# led_table_final.net
KiCad netlist of a schematic drawn in EAGLE
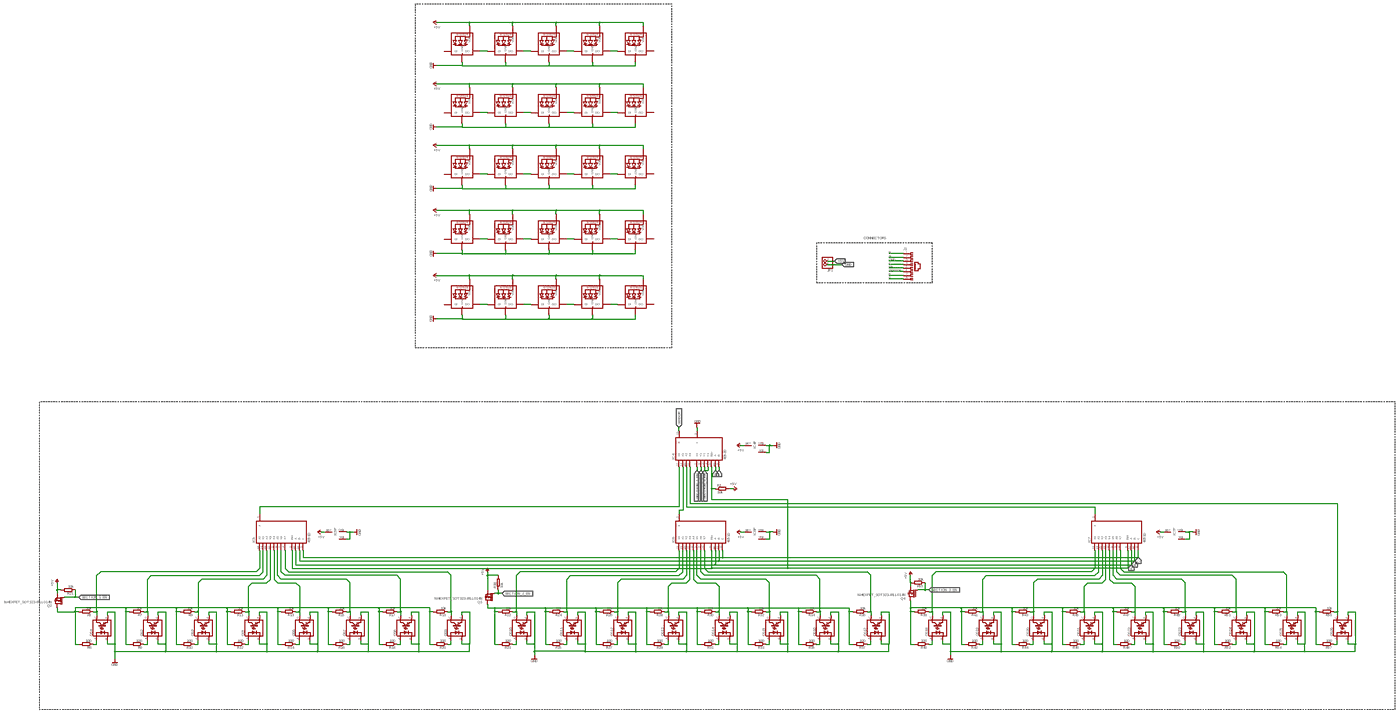
[diagram p0: schematic, sheet 1, overview]
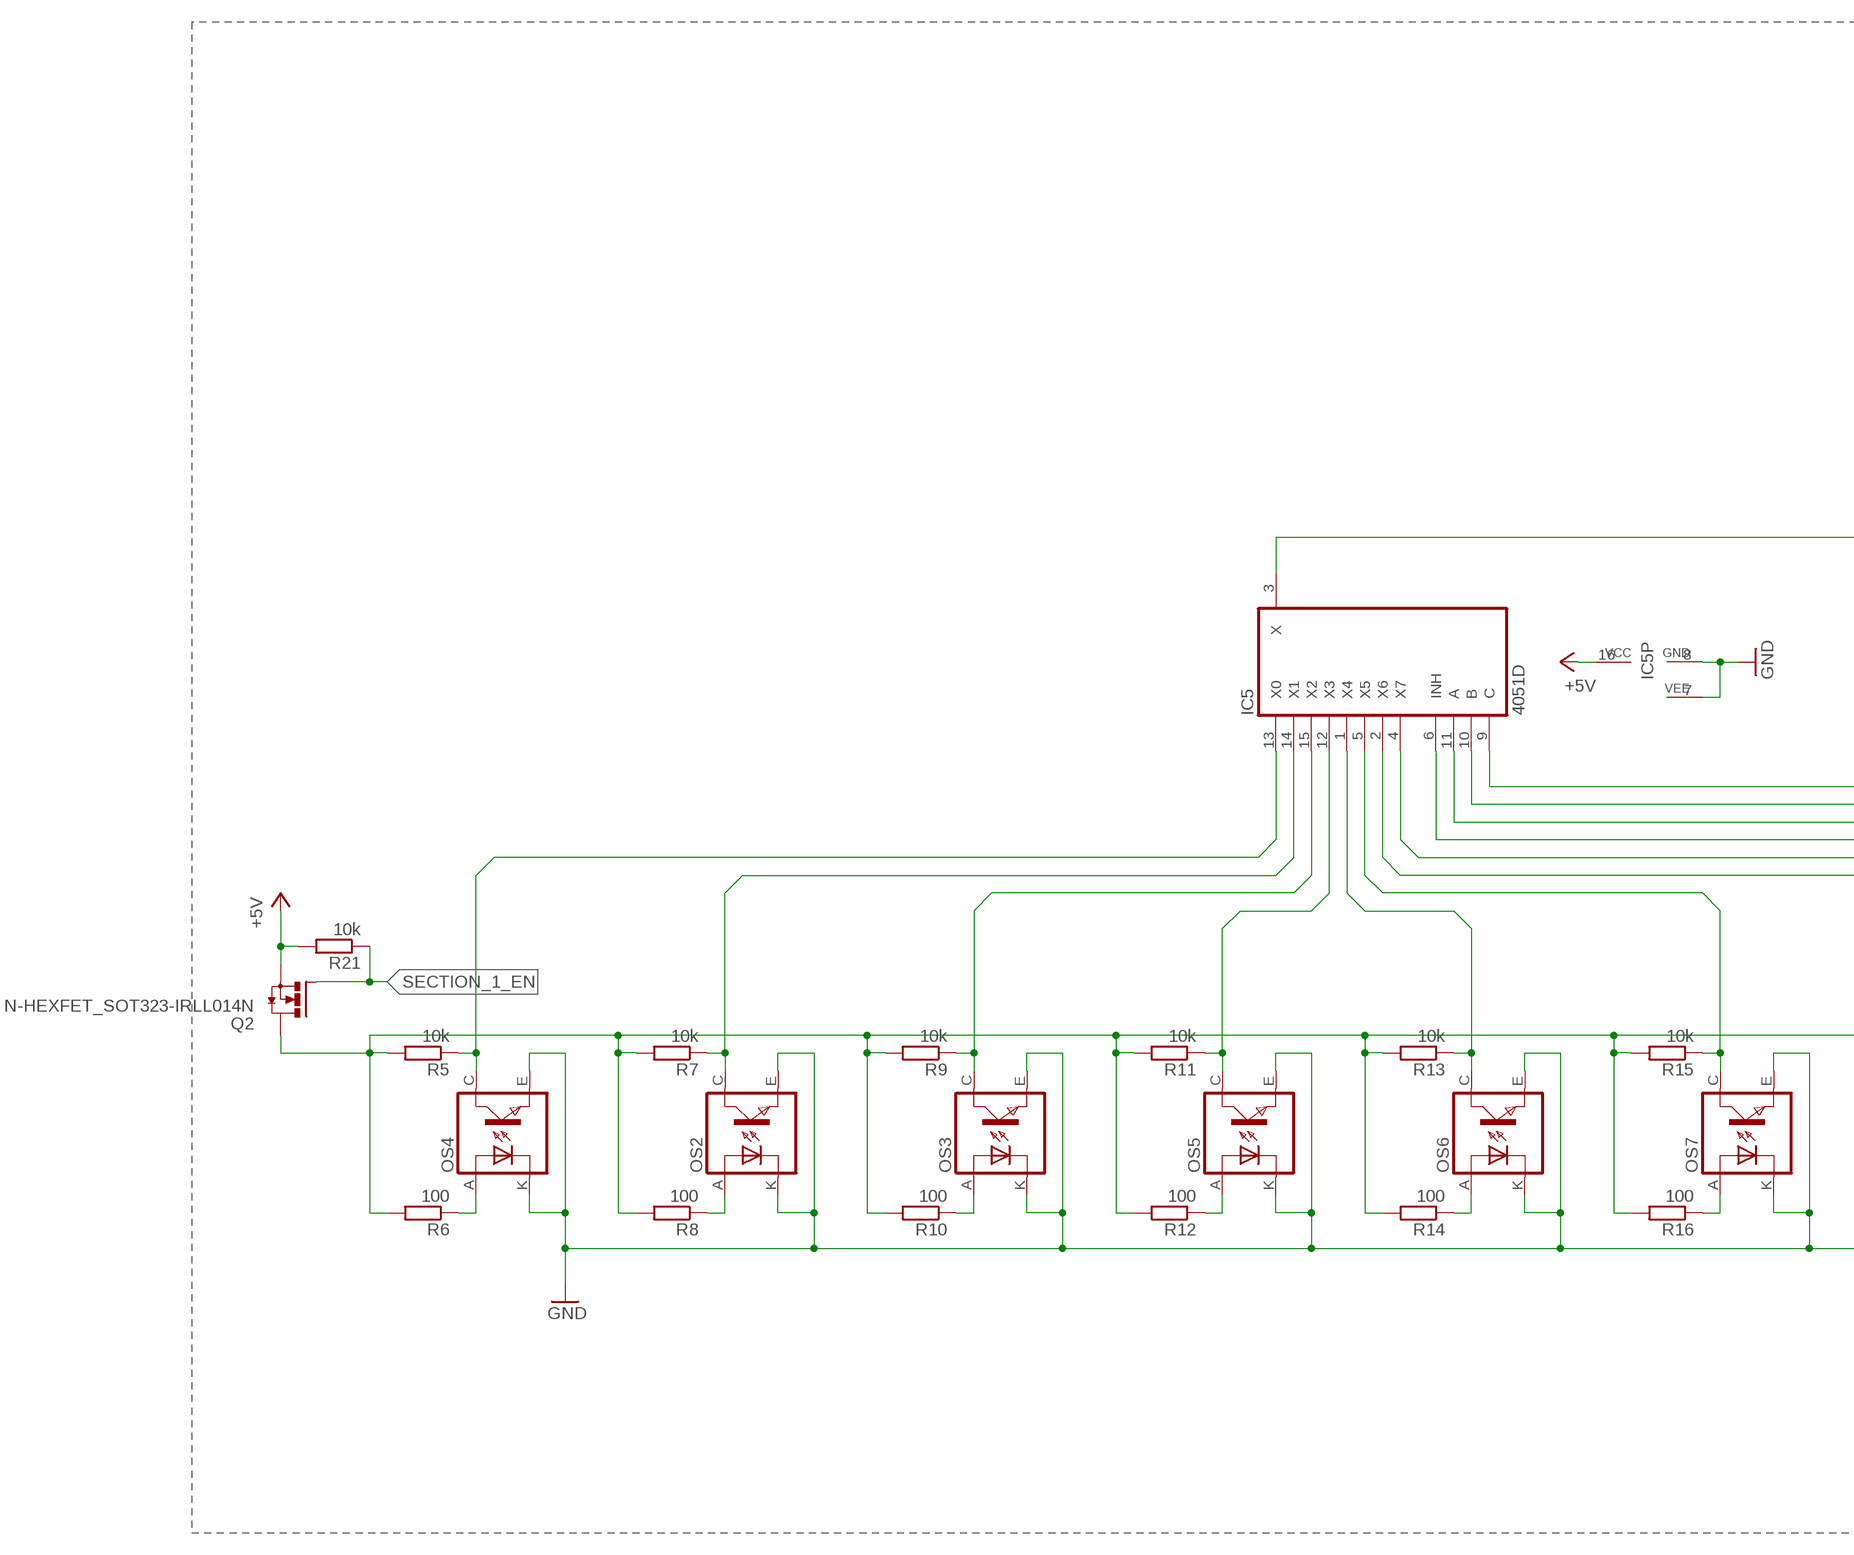
[diagram p1: schematic, sheet 1, part 1 of 4]
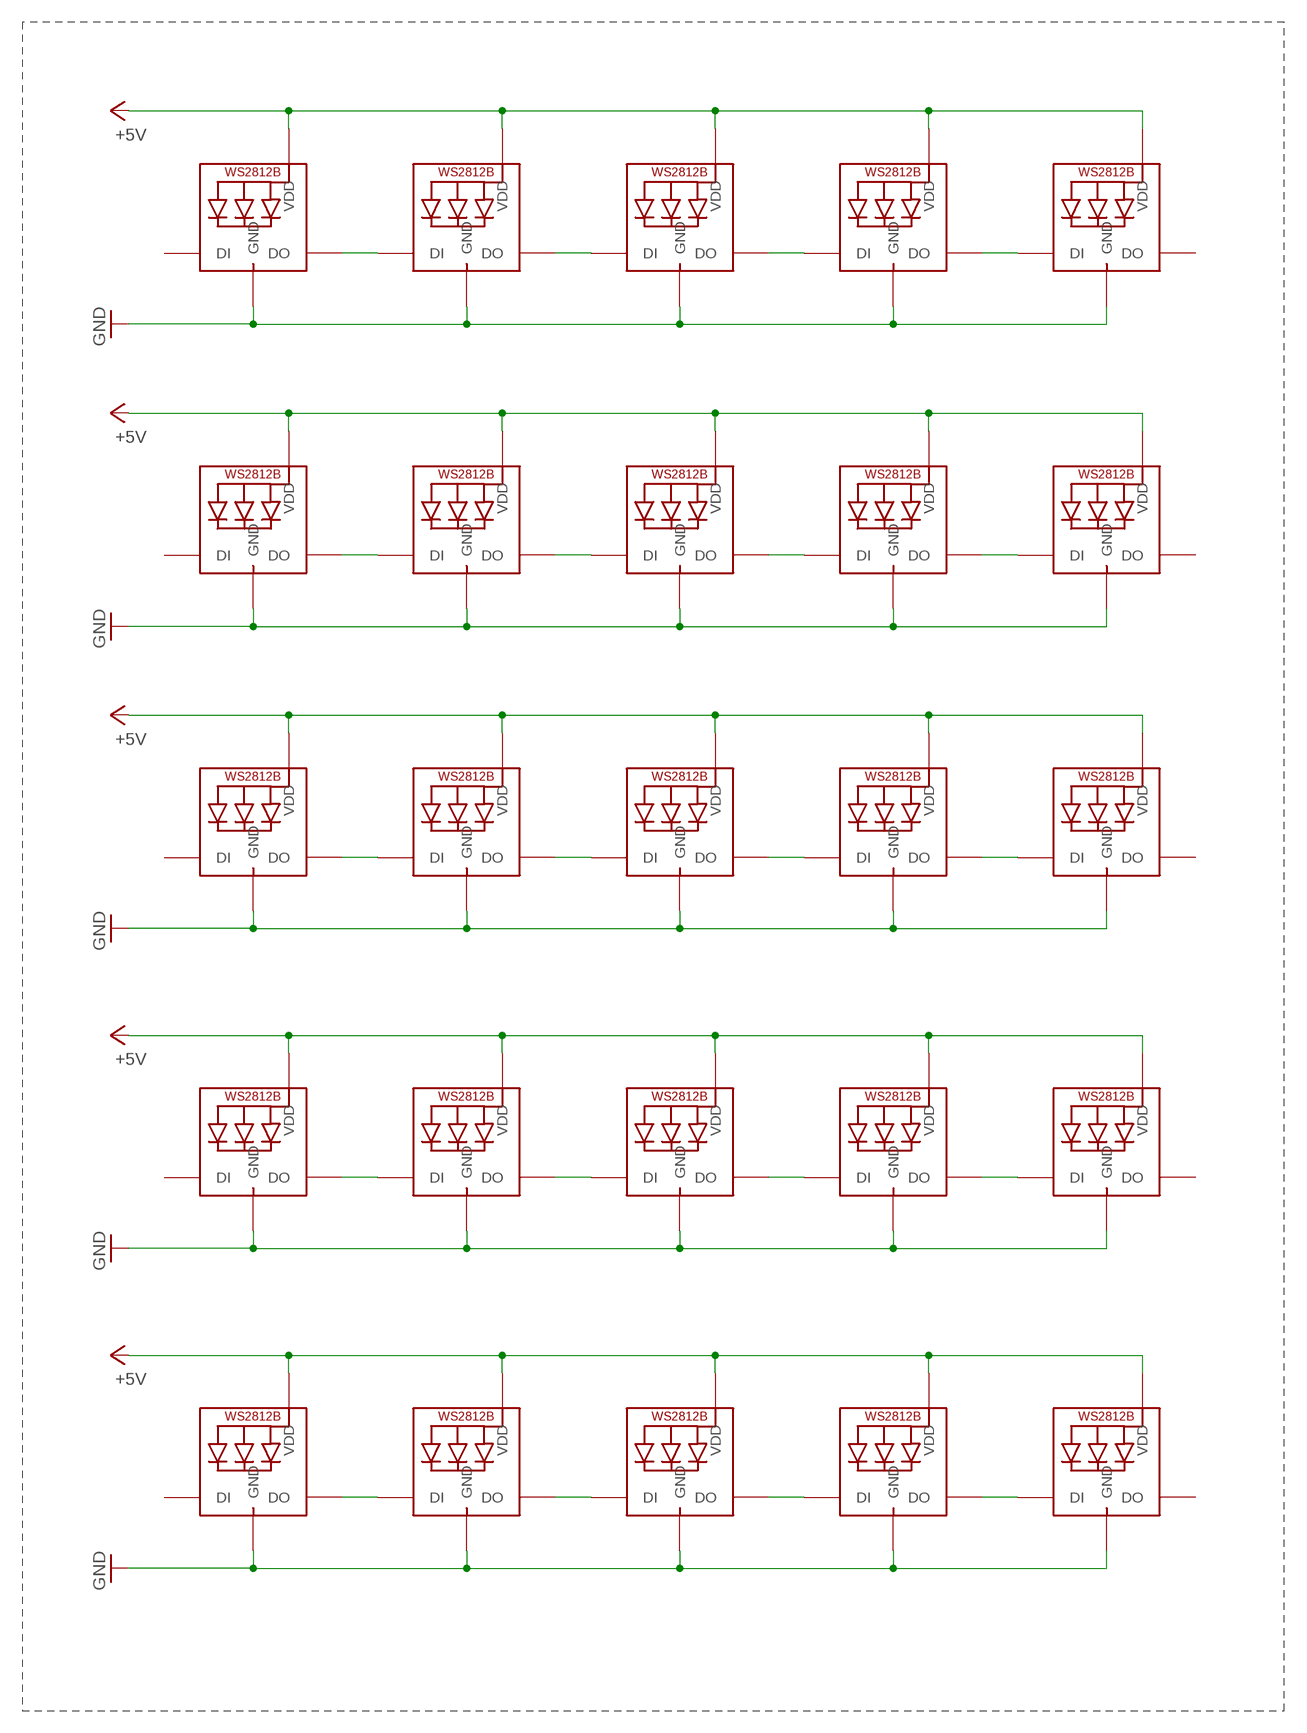
[diagram p2: schematic, sheet 1, part 2 of 4]
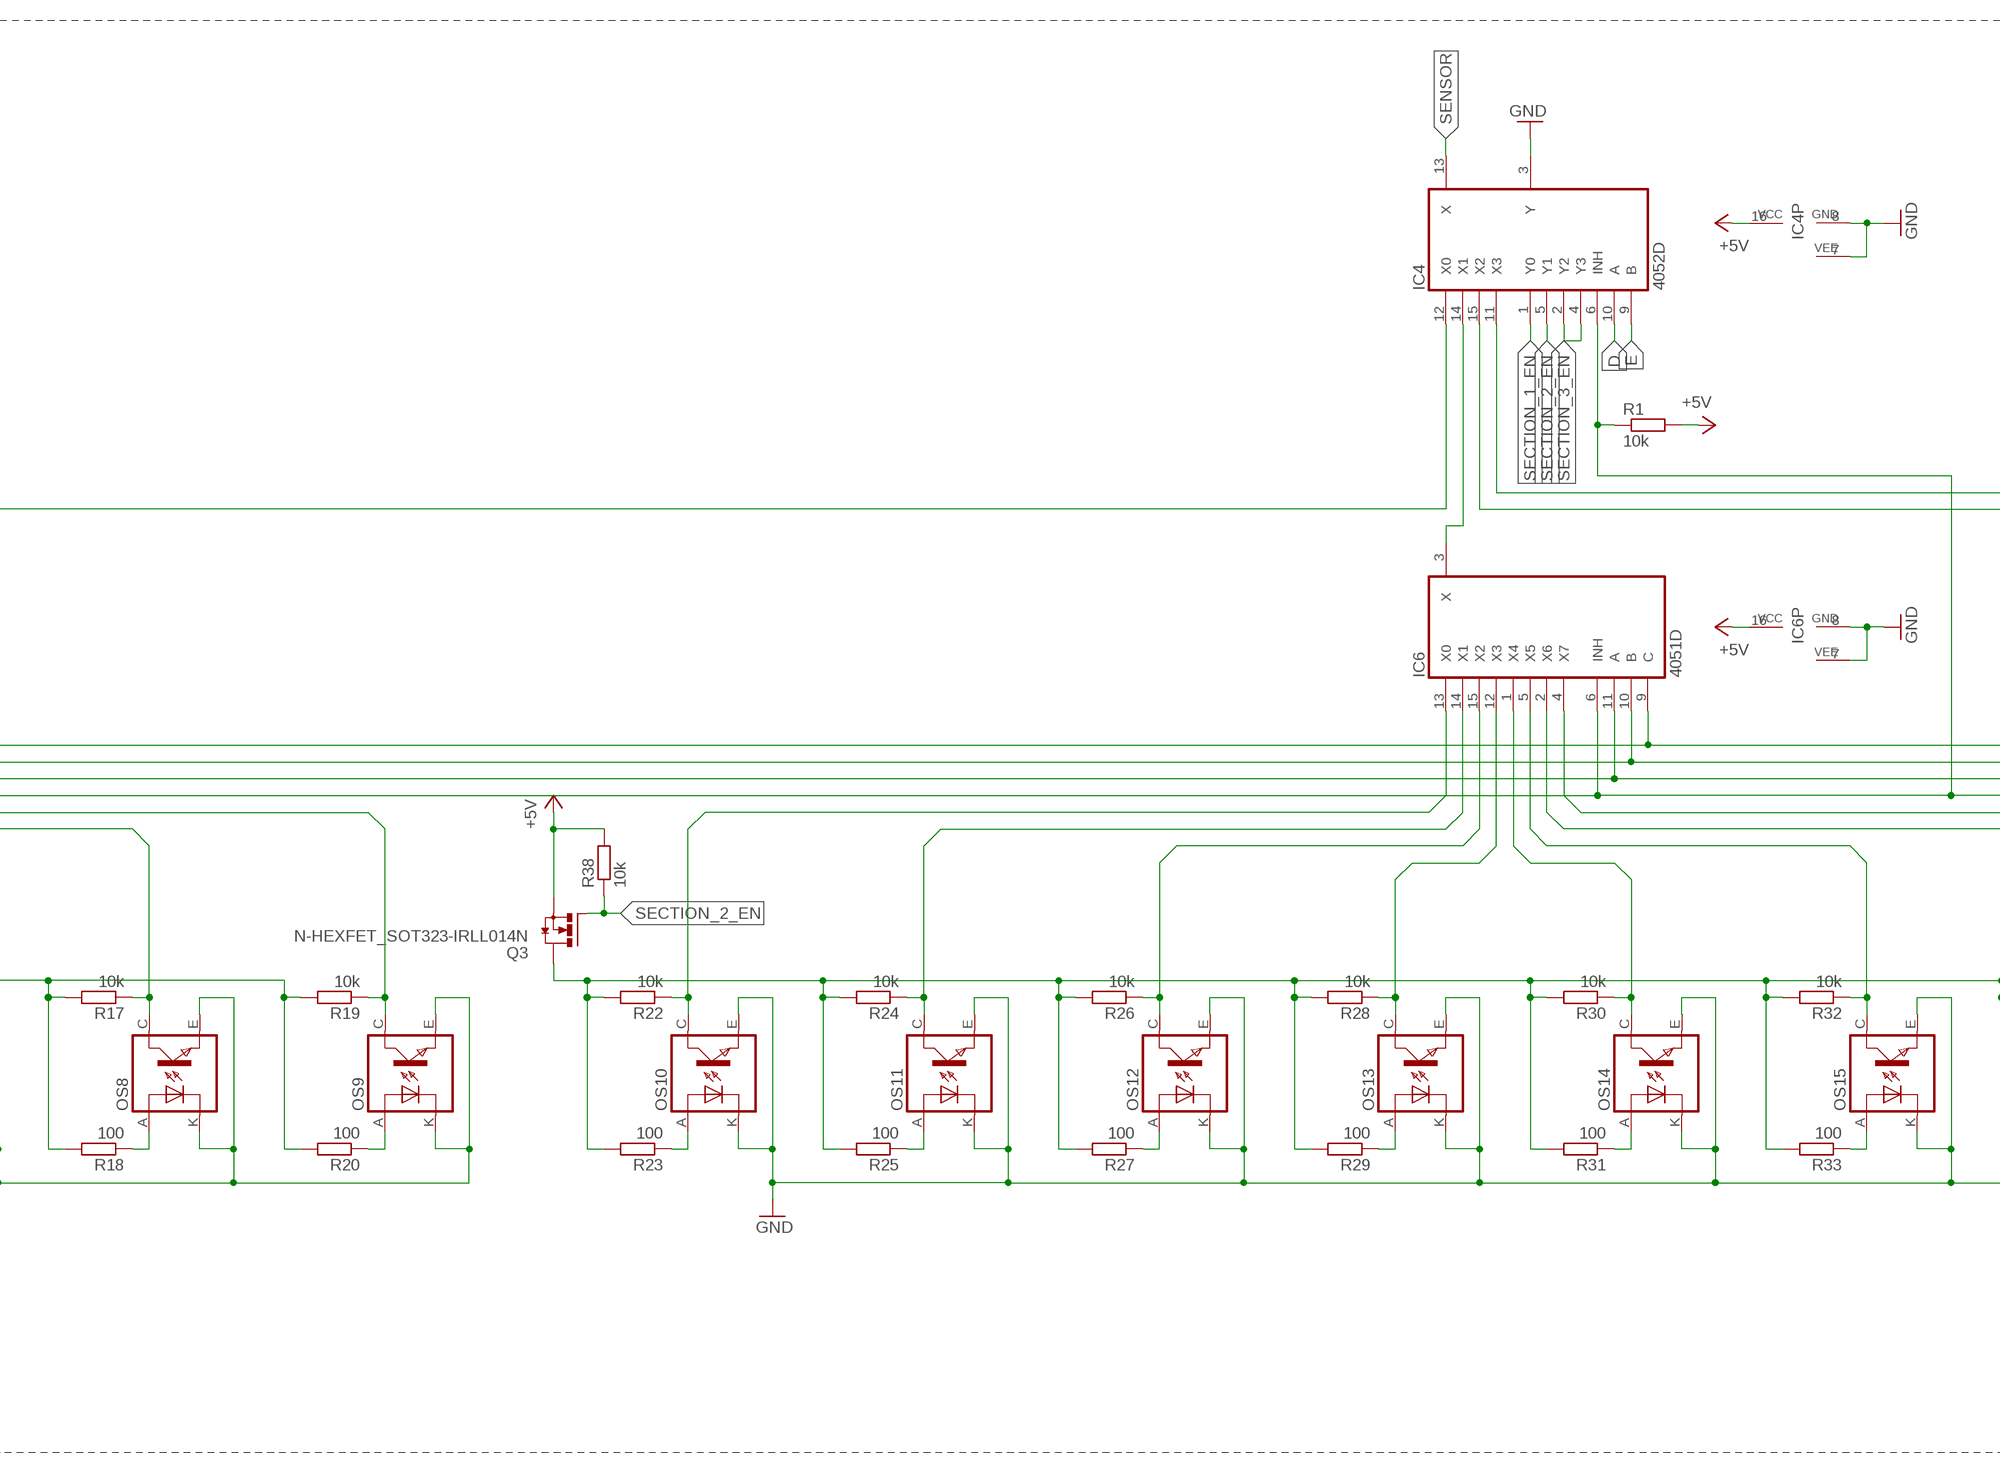
[diagram p3: schematic, sheet 1, part 3 of 4]
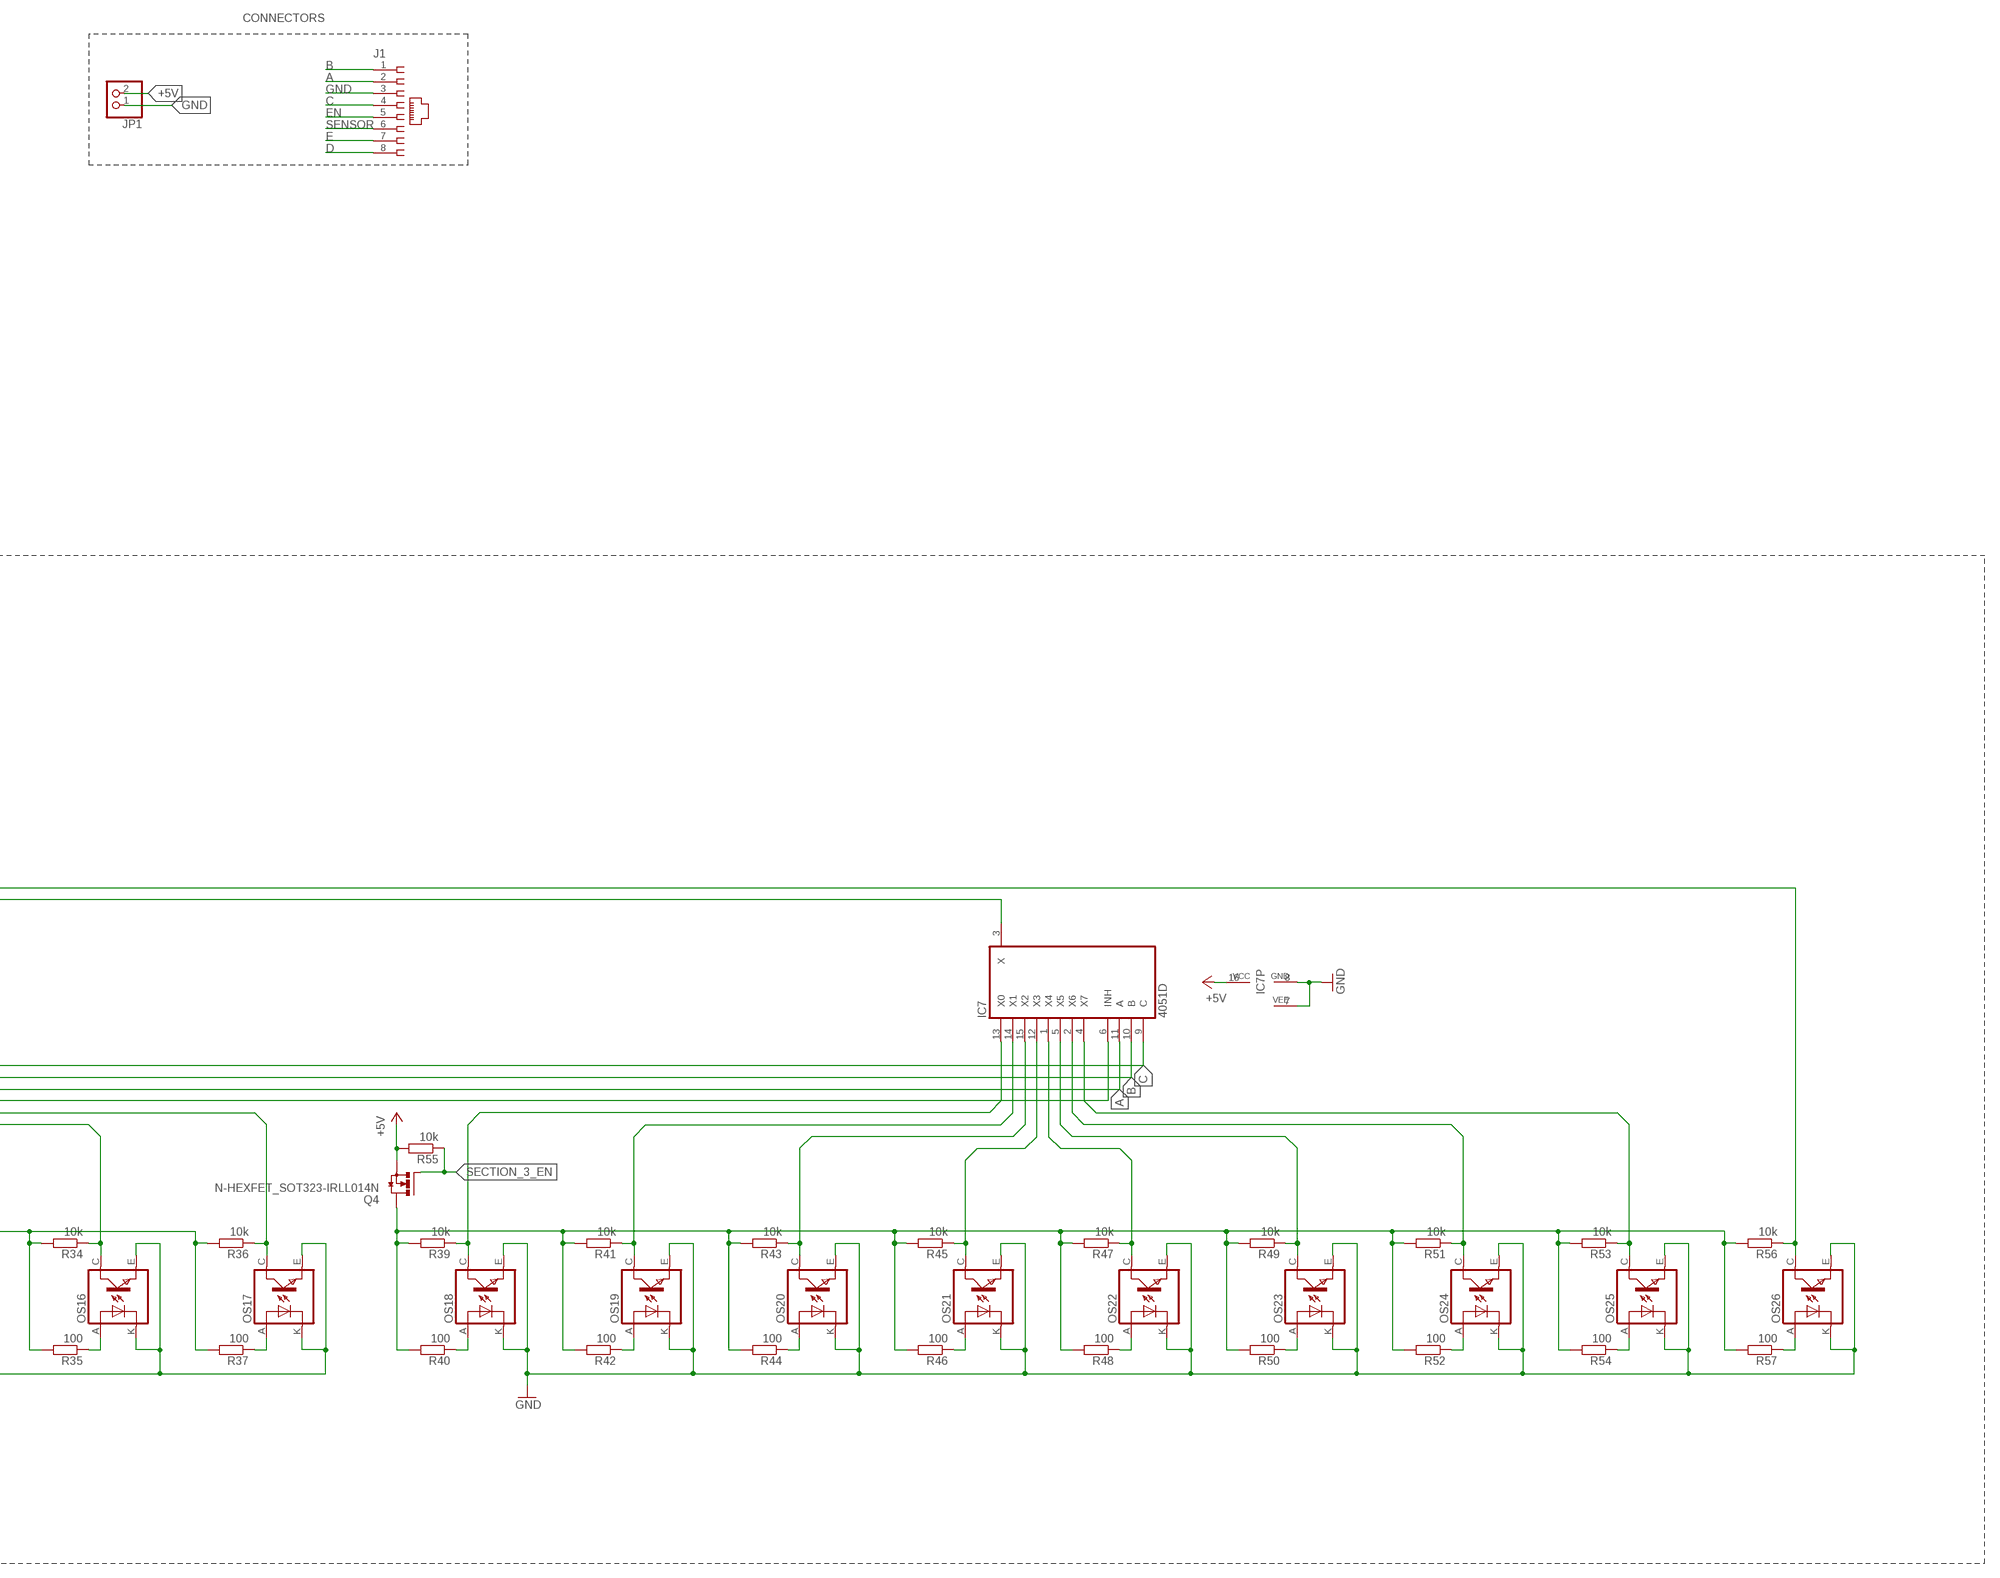
[diagram p4: schematic, sheet 1, part 4 of 4]

(export (version "E")
  (design (tool "Eeschema 10.0.6"))
  (components
    (comp (ref "IC4")
      (value "4052D")
      (footprint "eagle-import:SO16")
      (libsource (lib "eagle-import") (part "4052D"))
    )
    (comp (ref "IC5")
      (value "4051D")
      (footprint "eagle-import:SO16")
      (libsource (lib "eagle-import") (part "4051D"))
    )
    (comp (ref "IC6")
      (value "4051D")
      (footprint "eagle-import:SO16")
      (libsource (lib "eagle-import") (part "4051D"))
    )
    (comp (ref "IC7")
      (value "4051D")
      (footprint "eagle-import:SO16")
      (libsource (lib "eagle-import") (part "4051D"))
    )
    (comp (ref "J1")
      (value "556416-1")
      (footprint "eagle-import:556416-1")
      (libsource (lib "eagle-import") (part "556416-1"))
    )
    (comp (ref "JP1")
      (value "PINHD-1X2")
      (footprint "eagle-import:1X02")
      (libsource (lib "eagle-import") (part "PINHD-1X2"))
    )
    (comp (ref "LED1")
      (value "WS2812B")
      (footprint "eagle-import:WS2812B_ON_STRIP")
      (libsource (lib "eagle-import") (part "WS2812B"))
    )
    (comp (ref "LED2")
      (value "WS2812B")
      (footprint "eagle-import:WS2812B_ON_STRIP")
      (libsource (lib "eagle-import") (part "WS2812B"))
    )
    (comp (ref "LED3")
      (value "WS2812B")
      (footprint "eagle-import:WS2812B_ON_STRIP")
      (libsource (lib "eagle-import") (part "WS2812B"))
    )
    (comp (ref "LED4")
      (value "WS2812B")
      (footprint "eagle-import:WS2812B_ON_STRIP")
      (libsource (lib "eagle-import") (part "WS2812B"))
    )
    (comp (ref "LED5")
      (value "WS2812B")
      (footprint "eagle-import:WS2812B_ON_STRIP")
      (libsource (lib "eagle-import") (part "WS2812B"))
    )
    (comp (ref "LED6")
      (value "WS2812B")
      (footprint "eagle-import:WS2812B_ON_STRIP")
      (libsource (lib "eagle-import") (part "WS2812B"))
    )
    (comp (ref "LED7")
      (value "WS2812B")
      (footprint "eagle-import:WS2812B_ON_STRIP")
      (libsource (lib "eagle-import") (part "WS2812B"))
    )
    (comp (ref "LED8")
      (value "WS2812B")
      (footprint "eagle-import:WS2812B_ON_STRIP")
      (libsource (lib "eagle-import") (part "WS2812B"))
    )
    (comp (ref "LED9")
      (value "WS2812B")
      (footprint "eagle-import:WS2812B_ON_STRIP")
      (libsource (lib "eagle-import") (part "WS2812B"))
    )
    (comp (ref "LED10")
      (value "WS2812B")
      (footprint "eagle-import:WS2812B_ON_STRIP")
      (libsource (lib "eagle-import") (part "WS2812B"))
    )
    (comp (ref "LED11")
      (value "WS2812B")
      (footprint "eagle-import:WS2812B_ON_STRIP")
      (libsource (lib "eagle-import") (part "WS2812B"))
    )
    (comp (ref "LED12")
      (value "WS2812B")
      (footprint "eagle-import:WS2812B_ON_STRIP")
      (libsource (lib "eagle-import") (part "WS2812B"))
    )
    (comp (ref "LED13")
      (value "WS2812B")
      (footprint "eagle-import:WS2812B_ON_STRIP")
      (libsource (lib "eagle-import") (part "WS2812B"))
    )
    (comp (ref "LED14")
      (value "WS2812B")
      (footprint "eagle-import:WS2812B_ON_STRIP")
      (libsource (lib "eagle-import") (part "WS2812B"))
    )
    (comp (ref "LED15")
      (value "WS2812B")
      (footprint "eagle-import:WS2812B_ON_STRIP")
      (libsource (lib "eagle-import") (part "WS2812B"))
    )
    (comp (ref "LED16")
      (value "WS2812B")
      (footprint "eagle-import:WS2812B_ON_STRIP")
      (libsource (lib "eagle-import") (part "WS2812B"))
    )
    (comp (ref "LED17")
      (value "WS2812B")
      (footprint "eagle-import:WS2812B_ON_STRIP")
      (libsource (lib "eagle-import") (part "WS2812B"))
    )
    (comp (ref "LED18")
      (value "WS2812B")
      (footprint "eagle-import:WS2812B_ON_STRIP")
      (libsource (lib "eagle-import") (part "WS2812B"))
    )
    (comp (ref "LED19")
      (value "WS2812B")
      (footprint "eagle-import:WS2812B_ON_STRIP")
      (libsource (lib "eagle-import") (part "WS2812B"))
    )
    (comp (ref "LED20")
      (value "WS2812B")
      (footprint "eagle-import:WS2812B_ON_STRIP")
      (libsource (lib "eagle-import") (part "WS2812B"))
    )
    (comp (ref "LED21")
      (value "WS2812B")
      (footprint "eagle-import:WS2812B_ON_STRIP")
      (libsource (lib "eagle-import") (part "WS2812B"))
    )
    (comp (ref "LED22")
      (value "WS2812B")
      (footprint "eagle-import:WS2812B_ON_STRIP")
      (libsource (lib "eagle-import") (part "WS2812B"))
    )
    (comp (ref "LED23")
      (value "WS2812B")
      (footprint "eagle-import:WS2812B_ON_STRIP")
      (libsource (lib "eagle-import") (part "WS2812B"))
    )
    (comp (ref "LED24")
      (value "WS2812B")
      (footprint "eagle-import:WS2812B_ON_STRIP")
      (libsource (lib "eagle-import") (part "WS2812B"))
    )
    (comp (ref "LED25")
      (value "WS2812B")
      (footprint "eagle-import:WS2812B_ON_STRIP")
      (libsource (lib "eagle-import") (part "WS2812B"))
    )
    (comp (ref "OS2")
      (value "TCRT5000")
      (footprint "eagle-import:TCRT5000")
      (libsource (lib "eagle-import") (part "TCRT5000"))
    )
    (comp (ref "OS3")
      (value "TCRT5000")
      (footprint "eagle-import:TCRT5000")
      (libsource (lib "eagle-import") (part "TCRT5000"))
    )
    (comp (ref "OS4")
      (value "TCRT5000")
      (footprint "eagle-import:TCRT5000")
      (libsource (lib "eagle-import") (part "TCRT5000"))
    )
    (comp (ref "OS5")
      (value "TCRT5000")
      (footprint "eagle-import:TCRT5000")
      (libsource (lib "eagle-import") (part "TCRT5000"))
    )
    (comp (ref "OS6")
      (value "TCRT5000")
      (footprint "eagle-import:TCRT5000")
      (libsource (lib "eagle-import") (part "TCRT5000"))
    )
    (comp (ref "OS7")
      (value "TCRT5000")
      (footprint "eagle-import:TCRT5000")
      (libsource (lib "eagle-import") (part "TCRT5000"))
    )
    (comp (ref "OS8")
      (value "TCRT5000")
      (footprint "eagle-import:TCRT5000")
      (libsource (lib "eagle-import") (part "TCRT5000"))
    )
    (comp (ref "OS9")
      (value "TCRT5000")
      (footprint "eagle-import:TCRT5000")
      (libsource (lib "eagle-import") (part "TCRT5000"))
    )
    (comp (ref "OS10")
      (value "TCRT5000")
      (footprint "eagle-import:TCRT5000")
      (libsource (lib "eagle-import") (part "TCRT5000"))
    )
    (comp (ref "OS11")
      (value "TCRT5000")
      (footprint "eagle-import:TCRT5000")
      (libsource (lib "eagle-import") (part "TCRT5000"))
    )
    (comp (ref "OS12")
      (value "TCRT5000")
      (footprint "eagle-import:TCRT5000")
      (libsource (lib "eagle-import") (part "TCRT5000"))
    )
    (comp (ref "OS13")
      (value "TCRT5000")
      (footprint "eagle-import:TCRT5000")
      (libsource (lib "eagle-import") (part "TCRT5000"))
    )
    (comp (ref "OS14")
      (value "TCRT5000")
      (footprint "eagle-import:TCRT5000")
      (libsource (lib "eagle-import") (part "TCRT5000"))
    )
    (comp (ref "OS15")
      (value "TCRT5000")
      (footprint "eagle-import:TCRT5000")
      (libsource (lib "eagle-import") (part "TCRT5000"))
    )
    (comp (ref "OS16")
      (value "TCRT5000")
      (footprint "eagle-import:TCRT5000")
      (libsource (lib "eagle-import") (part "TCRT5000"))
    )
    (comp (ref "OS17")
      (value "TCRT5000")
      (footprint "eagle-import:TCRT5000")
      (libsource (lib "eagle-import") (part "TCRT5000"))
    )
    (comp (ref "OS18")
      (value "TCRT5000")
      (footprint "eagle-import:TCRT5000")
      (libsource (lib "eagle-import") (part "TCRT5000"))
    )
    (comp (ref "OS19")
      (value "TCRT5000")
      (footprint "eagle-import:TCRT5000")
      (libsource (lib "eagle-import") (part "TCRT5000"))
    )
    (comp (ref "OS20")
      (value "TCRT5000")
      (footprint "eagle-import:TCRT5000")
      (libsource (lib "eagle-import") (part "TCRT5000"))
    )
    (comp (ref "OS21")
      (value "TCRT5000")
      (footprint "eagle-import:TCRT5000")
      (libsource (lib "eagle-import") (part "TCRT5000"))
    )
    (comp (ref "OS22")
      (value "TCRT5000")
      (footprint "eagle-import:TCRT5000")
      (libsource (lib "eagle-import") (part "TCRT5000"))
    )
    (comp (ref "OS23")
      (value "TCRT5000")
      (footprint "eagle-import:TCRT5000")
      (libsource (lib "eagle-import") (part "TCRT5000"))
    )
    (comp (ref "OS24")
      (value "TCRT5000")
      (footprint "eagle-import:TCRT5000")
      (libsource (lib "eagle-import") (part "TCRT5000"))
    )
    (comp (ref "OS25")
      (value "TCRT5000")
      (footprint "eagle-import:TCRT5000")
      (libsource (lib "eagle-import") (part "TCRT5000"))
    )
    (comp (ref "OS26")
      (value "TCRT5000")
      (footprint "eagle-import:TCRT5000")
      (libsource (lib "eagle-import") (part "TCRT5000"))
    )
    (comp (ref "Q2")
      (value "N-HEXFET_SOT323-IRLL014N")
      (footprint "eagle-import:SOT223")
      (libsource (lib "eagle-import") (part "N-HEXFET_?-SOT323IRLL014N"))
    )
    (comp (ref "Q3")
      (value "N-HEXFET_SOT323-IRLL014N")
      (footprint "eagle-import:SOT223")
      (libsource (lib "eagle-import") (part "N-HEXFET_?-SOT323IRLL014N"))
    )
    (comp (ref "Q4")
      (value "N-HEXFET_SOT323-IRLL014N")
      (footprint "eagle-import:SOT223")
      (libsource (lib "eagle-import") (part "N-HEXFET_?-SOT323IRLL014N"))
    )
    (comp (ref "R1")
      (value "10k")
      (footprint "eagle-import:R1206")
      (libsource (lib "eagle-import") (part "R-EU_R1206"))
    )
    (comp (ref "R5")
      (value "10k")
      (footprint "eagle-import:R1206")
      (libsource (lib "eagle-import") (part "R-EU_R1206"))
    )
    (comp (ref "R6")
      (value "100")
      (footprint "eagle-import:R1206")
      (libsource (lib "eagle-import") (part "R-EU_R1206"))
    )
    (comp (ref "R7")
      (value "10k")
      (footprint "eagle-import:R1206")
      (libsource (lib "eagle-import") (part "R-EU_R1206"))
    )
    (comp (ref "R8")
      (value "100")
      (footprint "eagle-import:R1206")
      (libsource (lib "eagle-import") (part "R-EU_R1206"))
    )
    (comp (ref "R9")
      (value "10k")
      (footprint "eagle-import:R1206")
      (libsource (lib "eagle-import") (part "R-EU_R1206"))
    )
    (comp (ref "R10")
      (value "100")
      (footprint "eagle-import:R1206")
      (libsource (lib "eagle-import") (part "R-EU_R1206"))
    )
    (comp (ref "R11")
      (value "10k")
      (footprint "eagle-import:R1206")
      (libsource (lib "eagle-import") (part "R-EU_R1206"))
    )
    (comp (ref "R12")
      (value "100")
      (footprint "eagle-import:R1206")
      (libsource (lib "eagle-import") (part "R-EU_R1206"))
    )
    (comp (ref "R13")
      (value "10k")
      (footprint "eagle-import:R1206")
      (libsource (lib "eagle-import") (part "R-EU_R1206"))
    )
    (comp (ref "R14")
      (value "100")
      (footprint "eagle-import:R1206")
      (libsource (lib "eagle-import") (part "R-EU_R1206"))
    )
    (comp (ref "R15")
      (value "10k")
      (footprint "eagle-import:R1206")
      (libsource (lib "eagle-import") (part "R-EU_R1206"))
    )
    (comp (ref "R16")
      (value "100")
      (footprint "eagle-import:R1206")
      (libsource (lib "eagle-import") (part "R-EU_R1206"))
    )
    (comp (ref "R17")
      (value "10k")
      (footprint "eagle-import:R1206")
      (libsource (lib "eagle-import") (part "R-EU_R1206"))
    )
    (comp (ref "R18")
      (value "100")
      (footprint "eagle-import:R1206")
      (libsource (lib "eagle-import") (part "R-EU_R1206"))
    )
    (comp (ref "R19")
      (value "10k")
      (footprint "eagle-import:R1206")
      (libsource (lib "eagle-import") (part "R-EU_R1206"))
    )
    (comp (ref "R20")
      (value "100")
      (footprint "eagle-import:R1206")
      (libsource (lib "eagle-import") (part "R-EU_R1206"))
    )
    (comp (ref "R21")
      (value "10k")
      (footprint "eagle-import:R1206")
      (libsource (lib "eagle-import") (part "R-EU_R1206"))
    )
    (comp (ref "R22")
      (value "10k")
      (footprint "eagle-import:R1206")
      (libsource (lib "eagle-import") (part "R-EU_R1206"))
    )
    (comp (ref "R23")
      (value "100")
      (footprint "eagle-import:R1206")
      (libsource (lib "eagle-import") (part "R-EU_R1206"))
    )
    (comp (ref "R24")
      (value "10k")
      (footprint "eagle-import:R1206")
      (libsource (lib "eagle-import") (part "R-EU_R1206"))
    )
    (comp (ref "R25")
      (value "100")
      (footprint "eagle-import:R1206")
      (libsource (lib "eagle-import") (part "R-EU_R1206"))
    )
    (comp (ref "R26")
      (value "10k")
      (footprint "eagle-import:R1206")
      (libsource (lib "eagle-import") (part "R-EU_R1206"))
    )
    (comp (ref "R27")
      (value "100")
      (footprint "eagle-import:R1206")
      (libsource (lib "eagle-import") (part "R-EU_R1206"))
    )
    (comp (ref "R28")
      (value "10k")
      (footprint "eagle-import:R1206")
      (libsource (lib "eagle-import") (part "R-EU_R1206"))
    )
    (comp (ref "R29")
      (value "100")
      (footprint "eagle-import:R1206")
      (libsource (lib "eagle-import") (part "R-EU_R1206"))
    )
    (comp (ref "R30")
      (value "10k")
      (footprint "eagle-import:R1206")
      (libsource (lib "eagle-import") (part "R-EU_R1206"))
    )
    (comp (ref "R31")
      (value "100")
      (footprint "eagle-import:R1206")
      (libsource (lib "eagle-import") (part "R-EU_R1206"))
    )
    (comp (ref "R32")
      (value "10k")
      (footprint "eagle-import:R1206")
      (libsource (lib "eagle-import") (part "R-EU_R1206"))
    )
    (comp (ref "R33")
      (value "100")
      (footprint "eagle-import:R1206")
      (libsource (lib "eagle-import") (part "R-EU_R1206"))
    )
    (comp (ref "R34")
      (value "10k")
      (footprint "eagle-import:R1206")
      (libsource (lib "eagle-import") (part "R-EU_R1206"))
    )
    (comp (ref "R35")
      (value "100")
      (footprint "eagle-import:R1206")
      (libsource (lib "eagle-import") (part "R-EU_R1206"))
    )
    (comp (ref "R36")
      (value "10k")
      (footprint "eagle-import:R1206")
      (libsource (lib "eagle-import") (part "R-EU_R1206"))
    )
    (comp (ref "R37")
      (value "100")
      (footprint "eagle-import:R1206")
      (libsource (lib "eagle-import") (part "R-EU_R1206"))
    )
    (comp (ref "R38")
      (value "10k")
      (footprint "eagle-import:R1206")
      (libsource (lib "eagle-import") (part "R-EU_R1206"))
    )
    (comp (ref "R39")
      (value "10k")
      (footprint "eagle-import:R1206")
      (libsource (lib "eagle-import") (part "R-EU_R1206"))
    )
    (comp (ref "R40")
      (value "100")
      (footprint "eagle-import:R1206")
      (libsource (lib "eagle-import") (part "R-EU_R1206"))
    )
    (comp (ref "R41")
      (value "10k")
      (footprint "eagle-import:R1206")
      (libsource (lib "eagle-import") (part "R-EU_R1206"))
    )
    (comp (ref "R42")
      (value "100")
      (footprint "eagle-import:R1206")
      (libsource (lib "eagle-import") (part "R-EU_R1206"))
    )
    (comp (ref "R43")
      (value "10k")
      (footprint "eagle-import:R1206")
      (libsource (lib "eagle-import") (part "R-EU_R1206"))
    )
    (comp (ref "R44")
      (value "100")
      (footprint "eagle-import:R1206")
      (libsource (lib "eagle-import") (part "R-EU_R1206"))
    )
    (comp (ref "R45")
      (value "10k")
      (footprint "eagle-import:R1206")
      (libsource (lib "eagle-import") (part "R-EU_R1206"))
    )
    (comp (ref "R46")
      (value "100")
      (footprint "eagle-import:R1206")
      (libsource (lib "eagle-import") (part "R-EU_R1206"))
    )
    (comp (ref "R47")
      (value "10k")
      (footprint "eagle-import:R1206")
      (libsource (lib "eagle-import") (part "R-EU_R1206"))
    )
    (comp (ref "R48")
      (value "100")
      (footprint "eagle-import:R1206")
      (libsource (lib "eagle-import") (part "R-EU_R1206"))
    )
    (comp (ref "R49")
      (value "10k")
      (footprint "eagle-import:R1206")
      (libsource (lib "eagle-import") (part "R-EU_R1206"))
    )
    (comp (ref "R50")
      (value "100")
      (footprint "eagle-import:R1206")
      (libsource (lib "eagle-import") (part "R-EU_R1206"))
    )
    (comp (ref "R51")
      (value "10k")
      (footprint "eagle-import:R1206")
      (libsource (lib "eagle-import") (part "R-EU_R1206"))
    )
    (comp (ref "R52")
      (value "100")
      (footprint "eagle-import:R1206")
      (libsource (lib "eagle-import") (part "R-EU_R1206"))
    )
    (comp (ref "R53")
      (value "10k")
      (footprint "eagle-import:R1206")
      (libsource (lib "eagle-import") (part "R-EU_R1206"))
    )
    (comp (ref "R54")
      (value "100")
      (footprint "eagle-import:R1206")
      (libsource (lib "eagle-import") (part "R-EU_R1206"))
    )
    (comp (ref "R55")
      (value "10k")
      (footprint "eagle-import:R1206")
      (libsource (lib "eagle-import") (part "R-EU_R1206"))
    )
    (comp (ref "R56")
      (value "10k")
      (footprint "eagle-import:R1206")
      (libsource (lib "eagle-import") (part "R-EU_R1206"))
    )
    (comp (ref "R57")
      (value "100")
      (footprint "eagle-import:R1206")
      (libsource (lib "eagle-import") (part "R-EU_R1206"))
    )
  )
  (nets
    (net (code "1") (name "+5V") (class "Default")
      (node (ref "IC4") (pin "16") (pinfunction "VCC_16") (pintype "power_in"))
      (node (ref "IC5") (pin "16") (pinfunction "VCC_16") (pintype "power_in"))
      (node (ref "IC6") (pin "16") (pinfunction "VCC_16") (pintype "power_in"))
      (node (ref "IC7") (pin "16") (pinfunction "VCC_16") (pintype "power_in"))
      (node (ref "JP1") (pin "2") (pinfunction "2_2") (pintype "passive"))
      (node (ref "LED1") (pin "VCC_IN") (pinfunction "VDD_VCC_IN") (pintype "power_in"))
      (node (ref "LED1") (pin "VCC_OUT") (pinfunction "VDD_VCC_OUT") (pintype "power_in"))
      (node (ref "LED10") (pin "VCC_IN") (pinfunction "VDD_VCC_IN") (pintype "power_in"))
      (node (ref "LED10") (pin "VCC_OUT") (pinfunction "VDD_VCC_OUT") (pintype "power_in"))
      (node (ref "LED11") (pin "VCC_IN") (pinfunction "VDD_VCC_IN") (pintype "power_in"))
      (node (ref "LED11") (pin "VCC_OUT") (pinfunction "VDD_VCC_OUT") (pintype "power_in"))
      (node (ref "LED12") (pin "VCC_IN") (pinfunction "VDD_VCC_IN") (pintype "power_in"))
      (node (ref "LED12") (pin "VCC_OUT") (pinfunction "VDD_VCC_OUT") (pintype "power_in"))
      (node (ref "LED13") (pin "VCC_IN") (pinfunction "VDD_VCC_IN") (pintype "power_in"))
      (node (ref "LED13") (pin "VCC_OUT") (pinfunction "VDD_VCC_OUT") (pintype "power_in"))
      (node (ref "LED14") (pin "VCC_IN") (pinfunction "VDD_VCC_IN") (pintype "power_in"))
      (node (ref "LED14") (pin "VCC_OUT") (pinfunction "VDD_VCC_OUT") (pintype "power_in"))
      (node (ref "LED15") (pin "VCC_IN") (pinfunction "VDD_VCC_IN") (pintype "power_in"))
      (node (ref "LED15") (pin "VCC_OUT") (pinfunction "VDD_VCC_OUT") (pintype "power_in"))
      (node (ref "LED16") (pin "VCC_IN") (pinfunction "VDD_VCC_IN") (pintype "power_in"))
      (node (ref "LED16") (pin "VCC_OUT") (pinfunction "VDD_VCC_OUT") (pintype "power_in"))
      (node (ref "LED17") (pin "VCC_IN") (pinfunction "VDD_VCC_IN") (pintype "power_in"))
      (node (ref "LED17") (pin "VCC_OUT") (pinfunction "VDD_VCC_OUT") (pintype "power_in"))
      (node (ref "LED18") (pin "VCC_IN") (pinfunction "VDD_VCC_IN") (pintype "power_in"))
      (node (ref "LED18") (pin "VCC_OUT") (pinfunction "VDD_VCC_OUT") (pintype "power_in"))
      (node (ref "LED19") (pin "VCC_IN") (pinfunction "VDD_VCC_IN") (pintype "power_in"))
      (node (ref "LED19") (pin "VCC_OUT") (pinfunction "VDD_VCC_OUT") (pintype "power_in"))
      (node (ref "LED2") (pin "VCC_IN") (pinfunction "VDD_VCC_IN") (pintype "power_in"))
      (node (ref "LED2") (pin "VCC_OUT") (pinfunction "VDD_VCC_OUT") (pintype "power_in"))
      (node (ref "LED20") (pin "VCC_IN") (pinfunction "VDD_VCC_IN") (pintype "power_in"))
      (node (ref "LED20") (pin "VCC_OUT") (pinfunction "VDD_VCC_OUT") (pintype "power_in"))
      (node (ref "LED21") (pin "VCC_IN") (pinfunction "VDD_VCC_IN") (pintype "power_in"))
      (node (ref "LED21") (pin "VCC_OUT") (pinfunction "VDD_VCC_OUT") (pintype "power_in"))
      (node (ref "LED22") (pin "VCC_IN") (pinfunction "VDD_VCC_IN") (pintype "power_in"))
      (node (ref "LED22") (pin "VCC_OUT") (pinfunction "VDD_VCC_OUT") (pintype "power_in"))
      (node (ref "LED23") (pin "VCC_IN") (pinfunction "VDD_VCC_IN") (pintype "power_in"))
      (node (ref "LED23") (pin "VCC_OUT") (pinfunction "VDD_VCC_OUT") (pintype "power_in"))
      (node (ref "LED24") (pin "VCC_IN") (pinfunction "VDD_VCC_IN") (pintype "power_in"))
      (node (ref "LED24") (pin "VCC_OUT") (pinfunction "VDD_VCC_OUT") (pintype "power_in"))
      (node (ref "LED25") (pin "VCC_IN") (pinfunction "VDD_VCC_IN") (pintype "power_in"))
      (node (ref "LED25") (pin "VCC_OUT") (pinfunction "VDD_VCC_OUT") (pintype "power_in"))
      (node (ref "LED3") (pin "VCC_IN") (pinfunction "VDD_VCC_IN") (pintype "power_in"))
      (node (ref "LED3") (pin "VCC_OUT") (pinfunction "VDD_VCC_OUT") (pintype "power_in"))
      (node (ref "LED4") (pin "VCC_IN") (pinfunction "VDD_VCC_IN") (pintype "power_in"))
      (node (ref "LED4") (pin "VCC_OUT") (pinfunction "VDD_VCC_OUT") (pintype "power_in"))
      (node (ref "LED5") (pin "VCC_IN") (pinfunction "VDD_VCC_IN") (pintype "power_in"))
      (node (ref "LED5") (pin "VCC_OUT") (pinfunction "VDD_VCC_OUT") (pintype "power_in"))
      (node (ref "LED6") (pin "VCC_IN") (pinfunction "VDD_VCC_IN") (pintype "power_in"))
      (node (ref "LED6") (pin "VCC_OUT") (pinfunction "VDD_VCC_OUT") (pintype "power_in"))
      (node (ref "LED7") (pin "VCC_IN") (pinfunction "VDD_VCC_IN") (pintype "power_in"))
      (node (ref "LED7") (pin "VCC_OUT") (pinfunction "VDD_VCC_OUT") (pintype "power_in"))
      (node (ref "LED8") (pin "VCC_IN") (pinfunction "VDD_VCC_IN") (pintype "power_in"))
      (node (ref "LED8") (pin "VCC_OUT") (pinfunction "VDD_VCC_OUT") (pintype "power_in"))
      (node (ref "LED9") (pin "VCC_IN") (pinfunction "VDD_VCC_IN") (pintype "power_in"))
      (node (ref "LED9") (pin "VCC_OUT") (pinfunction "VDD_VCC_OUT") (pintype "power_in"))
      (node (ref "Q2") (pin "3") (pinfunction "S_3") (pintype "passive"))
      (node (ref "Q3") (pin "3") (pinfunction "S_3") (pintype "passive"))
      (node (ref "Q4") (pin "3") (pinfunction "S_3") (pintype "passive"))
      (node (ref "R1") (pin "2") (pinfunction "2_2") (pintype "passive"))
      (node (ref "R21") (pin "2") (pinfunction "2_2") (pintype "passive"))
      (node (ref "R38") (pin "2") (pinfunction "2_2") (pintype "passive"))
      (node (ref "R55") (pin "2") (pinfunction "2_2") (pintype "passive"))
    )
    (net (code "2") (name "/EN") (class "Default")
      (node (ref "IC4") (pin "6") (pinfunction "INH_6") (pintype "input"))
      (node (ref "IC5") (pin "6") (pinfunction "INH_6") (pintype "input"))
      (node (ref "IC6") (pin "6") (pinfunction "INH_6") (pintype "input"))
      (node (ref "IC7") (pin "6") (pinfunction "INH_6") (pintype "input"))
      (node (ref "J1") (pin "5") (pinfunction "5_5") (pintype "passive"))
      (node (ref "R1") (pin "1") (pinfunction "1_1") (pintype "passive"))
    )
    (net (code "3") (name "A") (class "Default")
      (node (ref "IC5") (pin "11") (pinfunction "A_11") (pintype "input"))
      (node (ref "IC6") (pin "11") (pinfunction "A_11") (pintype "input"))
      (node (ref "IC7") (pin "11") (pinfunction "A_11") (pintype "input"))
      (node (ref "J1") (pin "2") (pinfunction "2_2") (pintype "passive"))
    )
    (net (code "4") (name "B") (class "Default")
      (node (ref "IC5") (pin "10") (pinfunction "B_10") (pintype "input"))
      (node (ref "IC6") (pin "10") (pinfunction "B_10") (pintype "input"))
      (node (ref "IC7") (pin "10") (pinfunction "B_10") (pintype "input"))
      (node (ref "J1") (pin "1") (pinfunction "1_1") (pintype "passive"))
    )
    (net (code "5") (name "C") (class "Default")
      (node (ref "IC5") (pin "9") (pinfunction "C_9") (pintype "input"))
      (node (ref "IC6") (pin "9") (pinfunction "C_9") (pintype "input"))
      (node (ref "IC7") (pin "9") (pinfunction "C_9") (pintype "input"))
      (node (ref "J1") (pin "4") (pinfunction "4_4") (pintype "passive"))
    )
    (net (code "6") (name "D") (class "Default")
      (node (ref "IC4") (pin "10") (pinfunction "A_10") (pintype "input"))
      (node (ref "J1") (pin "8") (pinfunction "8_8") (pintype "passive"))
    )
    (net (code "7") (name "E") (class "Default")
      (node (ref "IC4") (pin "9") (pinfunction "B_9") (pintype "input"))
      (node (ref "J1") (pin "7") (pinfunction "7_7") (pintype "passive"))
    )
    (net (code "8") (name "GND") (class "Default")
      (node (ref "IC4") (pin "3") (pinfunction "Y_3") (pintype "bidirectional"))
      (node (ref "IC4") (pin "7") (pinfunction "VEE_7") (pintype "power_in"))
      (node (ref "IC4") (pin "8") (pinfunction "GND_8") (pintype "power_in"))
      (node (ref "IC5") (pin "7") (pinfunction "VEE_7") (pintype "power_in"))
      (node (ref "IC5") (pin "8") (pinfunction "GND_8") (pintype "power_in"))
      (node (ref "IC6") (pin "7") (pinfunction "VEE_7") (pintype "power_in"))
      (node (ref "IC6") (pin "8") (pinfunction "GND_8") (pintype "power_in"))
      (node (ref "IC7") (pin "7") (pinfunction "VEE_7") (pintype "power_in"))
      (node (ref "IC7") (pin "8") (pinfunction "GND_8") (pintype "power_in"))
      (node (ref "J1") (pin "3") (pinfunction "3_3") (pintype "passive"))
      (node (ref "JP1") (pin "1") (pinfunction "1_1") (pintype "passive"))
      (node (ref "LED1") (pin "GND_IN") (pinfunction "GND_GND_IN") (pintype "power_in"))
      (node (ref "LED1") (pin "GND_OUT") (pinfunction "GND_GND_OUT") (pintype "power_in"))
      (node (ref "LED10") (pin "GND_IN") (pinfunction "GND_GND_IN") (pintype "power_in"))
      (node (ref "LED10") (pin "GND_OUT") (pinfunction "GND_GND_OUT") (pintype "power_in"))
      (node (ref "LED11") (pin "GND_IN") (pinfunction "GND_GND_IN") (pintype "power_in"))
      (node (ref "LED11") (pin "GND_OUT") (pinfunction "GND_GND_OUT") (pintype "power_in"))
      (node (ref "LED12") (pin "GND_IN") (pinfunction "GND_GND_IN") (pintype "power_in"))
      (node (ref "LED12") (pin "GND_OUT") (pinfunction "GND_GND_OUT") (pintype "power_in"))
      (node (ref "LED13") (pin "GND_IN") (pinfunction "GND_GND_IN") (pintype "power_in"))
      (node (ref "LED13") (pin "GND_OUT") (pinfunction "GND_GND_OUT") (pintype "power_in"))
      (node (ref "LED14") (pin "GND_IN") (pinfunction "GND_GND_IN") (pintype "power_in"))
      (node (ref "LED14") (pin "GND_OUT") (pinfunction "GND_GND_OUT") (pintype "power_in"))
      (node (ref "LED15") (pin "GND_IN") (pinfunction "GND_GND_IN") (pintype "power_in"))
      (node (ref "LED15") (pin "GND_OUT") (pinfunction "GND_GND_OUT") (pintype "power_in"))
      (node (ref "LED16") (pin "GND_IN") (pinfunction "GND_GND_IN") (pintype "power_in"))
      (node (ref "LED16") (pin "GND_OUT") (pinfunction "GND_GND_OUT") (pintype "power_in"))
      (node (ref "LED17") (pin "GND_IN") (pinfunction "GND_GND_IN") (pintype "power_in"))
      (node (ref "LED17") (pin "GND_OUT") (pinfunction "GND_GND_OUT") (pintype "power_in"))
      (node (ref "LED18") (pin "GND_IN") (pinfunction "GND_GND_IN") (pintype "power_in"))
      (node (ref "LED18") (pin "GND_OUT") (pinfunction "GND_GND_OUT") (pintype "power_in"))
      (node (ref "LED19") (pin "GND_IN") (pinfunction "GND_GND_IN") (pintype "power_in"))
      (node (ref "LED19") (pin "GND_OUT") (pinfunction "GND_GND_OUT") (pintype "power_in"))
      (node (ref "LED2") (pin "GND_IN") (pinfunction "GND_GND_IN") (pintype "power_in"))
      (node (ref "LED2") (pin "GND_OUT") (pinfunction "GND_GND_OUT") (pintype "power_in"))
      (node (ref "LED20") (pin "GND_IN") (pinfunction "GND_GND_IN") (pintype "power_in"))
      (node (ref "LED20") (pin "GND_OUT") (pinfunction "GND_GND_OUT") (pintype "power_in"))
      (node (ref "LED21") (pin "GND_IN") (pinfunction "GND_GND_IN") (pintype "power_in"))
      (node (ref "LED21") (pin "GND_OUT") (pinfunction "GND_GND_OUT") (pintype "power_in"))
      (node (ref "LED22") (pin "GND_IN") (pinfunction "GND_GND_IN") (pintype "power_in"))
      (node (ref "LED22") (pin "GND_OUT") (pinfunction "GND_GND_OUT") (pintype "power_in"))
      (node (ref "LED23") (pin "GND_IN") (pinfunction "GND_GND_IN") (pintype "power_in"))
      (node (ref "LED23") (pin "GND_OUT") (pinfunction "GND_GND_OUT") (pintype "power_in"))
      (node (ref "LED24") (pin "GND_IN") (pinfunction "GND_GND_IN") (pintype "power_in"))
      (node (ref "LED24") (pin "GND_OUT") (pinfunction "GND_GND_OUT") (pintype "power_in"))
      (node (ref "LED25") (pin "GND_IN") (pinfunction "GND_GND_IN") (pintype "power_in"))
      (node (ref "LED25") (pin "GND_OUT") (pinfunction "GND_GND_OUT") (pintype "power_in"))
      (node (ref "LED3") (pin "GND_IN") (pinfunction "GND_GND_IN") (pintype "power_in"))
      (node (ref "LED3") (pin "GND_OUT") (pinfunction "GND_GND_OUT") (pintype "power_in"))
      (node (ref "LED4") (pin "GND_IN") (pinfunction "GND_GND_IN") (pintype "power_in"))
      (node (ref "LED4") (pin "GND_OUT") (pinfunction "GND_GND_OUT") (pintype "power_in"))
      (node (ref "LED5") (pin "GND_IN") (pinfunction "GND_GND_IN") (pintype "power_in"))
      (node (ref "LED5") (pin "GND_OUT") (pinfunction "GND_GND_OUT") (pintype "power_in"))
      (node (ref "LED6") (pin "GND_IN") (pinfunction "GND_GND_IN") (pintype "power_in"))
      (node (ref "LED6") (pin "GND_OUT") (pinfunction "GND_GND_OUT") (pintype "power_in"))
      (node (ref "LED7") (pin "GND_IN") (pinfunction "GND_GND_IN") (pintype "power_in"))
      (node (ref "LED7") (pin "GND_OUT") (pinfunction "GND_GND_OUT") (pintype "power_in"))
      (node (ref "LED8") (pin "GND_IN") (pinfunction "GND_GND_IN") (pintype "power_in"))
      (node (ref "LED8") (pin "GND_OUT") (pinfunction "GND_GND_OUT") (pintype "power_in"))
      (node (ref "LED9") (pin "GND_IN") (pinfunction "GND_GND_IN") (pintype "power_in"))
      (node (ref "LED9") (pin "GND_OUT") (pinfunction "GND_GND_OUT") (pintype "power_in"))
      (node (ref "OS10") (pin "E") (pinfunction "EMITTER_E") (pintype "passive"))
      (node (ref "OS10") (pin "K") (pinfunction "CATHODE_K") (pintype "passive"))
      (node (ref "OS11") (pin "E") (pinfunction "EMITTER_E") (pintype "passive"))
      (node (ref "OS11") (pin "K") (pinfunction "CATHODE_K") (pintype "passive"))
      (node (ref "OS12") (pin "E") (pinfunction "EMITTER_E") (pintype "passive"))
      (node (ref "OS12") (pin "K") (pinfunction "CATHODE_K") (pintype "passive"))
      (node (ref "OS13") (pin "E") (pinfunction "EMITTER_E") (pintype "passive"))
      (node (ref "OS13") (pin "K") (pinfunction "CATHODE_K") (pintype "passive"))
      (node (ref "OS14") (pin "E") (pinfunction "EMITTER_E") (pintype "passive"))
      (node (ref "OS14") (pin "K") (pinfunction "CATHODE_K") (pintype "passive"))
      (node (ref "OS15") (pin "E") (pinfunction "EMITTER_E") (pintype "passive"))
      (node (ref "OS15") (pin "K") (pinfunction "CATHODE_K") (pintype "passive"))
      (node (ref "OS16") (pin "E") (pinfunction "EMITTER_E") (pintype "passive"))
      (node (ref "OS16") (pin "K") (pinfunction "CATHODE_K") (pintype "passive"))
      (node (ref "OS17") (pin "E") (pinfunction "EMITTER_E") (pintype "passive"))
      (node (ref "OS17") (pin "K") (pinfunction "CATHODE_K") (pintype "passive"))
      (node (ref "OS18") (pin "E") (pinfunction "EMITTER_E") (pintype "passive"))
      (node (ref "OS18") (pin "K") (pinfunction "CATHODE_K") (pintype "passive"))
      (node (ref "OS19") (pin "E") (pinfunction "EMITTER_E") (pintype "passive"))
      (node (ref "OS19") (pin "K") (pinfunction "CATHODE_K") (pintype "passive"))
      (node (ref "OS2") (pin "E") (pinfunction "EMITTER_E") (pintype "passive"))
      (node (ref "OS2") (pin "K") (pinfunction "CATHODE_K") (pintype "passive"))
      (node (ref "OS20") (pin "E") (pinfunction "EMITTER_E") (pintype "passive"))
      (node (ref "OS20") (pin "K") (pinfunction "CATHODE_K") (pintype "passive"))
      (node (ref "OS21") (pin "E") (pinfunction "EMITTER_E") (pintype "passive"))
      (node (ref "OS21") (pin "K") (pinfunction "CATHODE_K") (pintype "passive"))
      (node (ref "OS22") (pin "E") (pinfunction "EMITTER_E") (pintype "passive"))
      (node (ref "OS22") (pin "K") (pinfunction "CATHODE_K") (pintype "passive"))
      (node (ref "OS23") (pin "E") (pinfunction "EMITTER_E") (pintype "passive"))
      (node (ref "OS23") (pin "K") (pinfunction "CATHODE_K") (pintype "passive"))
      (node (ref "OS24") (pin "E") (pinfunction "EMITTER_E") (pintype "passive"))
      (node (ref "OS24") (pin "K") (pinfunction "CATHODE_K") (pintype "passive"))
      (node (ref "OS25") (pin "E") (pinfunction "EMITTER_E") (pintype "passive"))
      (node (ref "OS25") (pin "K") (pinfunction "CATHODE_K") (pintype "passive"))
      (node (ref "OS26") (pin "E") (pinfunction "EMITTER_E") (pintype "passive"))
      (node (ref "OS26") (pin "K") (pinfunction "CATHODE_K") (pintype "passive"))
      (node (ref "OS3") (pin "E") (pinfunction "EMITTER_E") (pintype "passive"))
      (node (ref "OS3") (pin "K") (pinfunction "CATHODE_K") (pintype "passive"))
      (node (ref "OS4") (pin "E") (pinfunction "EMITTER_E") (pintype "passive"))
      (node (ref "OS4") (pin "K") (pinfunction "CATHODE_K") (pintype "passive"))
      (node (ref "OS5") (pin "E") (pinfunction "EMITTER_E") (pintype "passive"))
      (node (ref "OS5") (pin "K") (pinfunction "CATHODE_K") (pintype "passive"))
      (node (ref "OS6") (pin "E") (pinfunction "EMITTER_E") (pintype "passive"))
      (node (ref "OS6") (pin "K") (pinfunction "CATHODE_K") (pintype "passive"))
      (node (ref "OS7") (pin "E") (pinfunction "EMITTER_E") (pintype "passive"))
      (node (ref "OS7") (pin "K") (pinfunction "CATHODE_K") (pintype "passive"))
      (node (ref "OS8") (pin "E") (pinfunction "EMITTER_E") (pintype "passive"))
      (node (ref "OS8") (pin "K") (pinfunction "CATHODE_K") (pintype "passive"))
      (node (ref "OS9") (pin "E") (pinfunction "EMITTER_E") (pintype "passive"))
      (node (ref "OS9") (pin "K") (pinfunction "CATHODE_K") (pintype "passive"))
    )
    (net (code "9") (name "Net-(IC4A-X0)") (class "Default")
      (node (ref "IC4") (pin "12") (pinfunction "X0_12") (pintype "bidirectional"))
      (node (ref "IC5") (pin "3") (pinfunction "X_3") (pintype "bidirectional"))
    )
    (net (code "10") (name "Net-(IC4A-X1)") (class "Default")
      (node (ref "IC4") (pin "14") (pinfunction "X1_14") (pintype "bidirectional"))
      (node (ref "IC6") (pin "3") (pinfunction "X_3") (pintype "bidirectional"))
    )
    (net (code "11") (name "Net-(IC4A-X2)") (class "Default")
      (node (ref "IC4") (pin "15") (pinfunction "X2_15") (pintype "bidirectional"))
      (node (ref "IC7") (pin "3") (pinfunction "X_3") (pintype "bidirectional"))
    )
    (net (code "12") (name "Net-(IC4A-X3)") (class "Default")
      (node (ref "IC4") (pin "11") (pinfunction "X3_11") (pintype "bidirectional"))
      (node (ref "OS26") (pin "C") (pinfunction "COLLECTOR_C") (pintype "passive"))
      (node (ref "R56") (pin "1") (pinfunction "1_1") (pintype "passive"))
    )
    (net (code "13") (name "Net-(IC5A-X0)") (class "Default")
      (node (ref "IC5") (pin "13") (pinfunction "X0_13") (pintype "bidirectional"))
      (node (ref "OS4") (pin "C") (pinfunction "COLLECTOR_C") (pintype "passive"))
      (node (ref "R5") (pin "1") (pinfunction "1_1") (pintype "passive"))
    )
    (net (code "14") (name "Net-(IC5A-X1)") (class "Default")
      (node (ref "IC5") (pin "14") (pinfunction "X1_14") (pintype "bidirectional"))
      (node (ref "OS2") (pin "C") (pinfunction "COLLECTOR_C") (pintype "passive"))
      (node (ref "R7") (pin "1") (pinfunction "1_1") (pintype "passive"))
    )
    (net (code "15") (name "Net-(IC5A-X2)") (class "Default")
      (node (ref "IC5") (pin "15") (pinfunction "X2_15") (pintype "bidirectional"))
      (node (ref "OS3") (pin "C") (pinfunction "COLLECTOR_C") (pintype "passive"))
      (node (ref "R9") (pin "1") (pinfunction "1_1") (pintype "passive"))
    )
    (net (code "16") (name "Net-(IC5A-X3)") (class "Default")
      (node (ref "IC5") (pin "12") (pinfunction "X3_12") (pintype "bidirectional"))
      (node (ref "OS5") (pin "C") (pinfunction "COLLECTOR_C") (pintype "passive"))
      (node (ref "R11") (pin "1") (pinfunction "1_1") (pintype "passive"))
    )
    (net (code "17") (name "Net-(IC5A-X4)") (class "Default")
      (node (ref "IC5") (pin "1") (pinfunction "X4_1") (pintype "bidirectional"))
      (node (ref "OS6") (pin "C") (pinfunction "COLLECTOR_C") (pintype "passive"))
      (node (ref "R13") (pin "1") (pinfunction "1_1") (pintype "passive"))
    )
    (net (code "18") (name "Net-(IC5A-X5)") (class "Default")
      (node (ref "IC5") (pin "5") (pinfunction "X5_5") (pintype "bidirectional"))
      (node (ref "OS7") (pin "C") (pinfunction "COLLECTOR_C") (pintype "passive"))
      (node (ref "R15") (pin "1") (pinfunction "1_1") (pintype "passive"))
    )
    (net (code "19") (name "Net-(IC5A-X6)") (class "Default")
      (node (ref "IC5") (pin "2") (pinfunction "X6_2") (pintype "bidirectional"))
      (node (ref "OS8") (pin "C") (pinfunction "COLLECTOR_C") (pintype "passive"))
      (node (ref "R17") (pin "1") (pinfunction "1_1") (pintype "passive"))
    )
    (net (code "20") (name "Net-(IC5A-X7)") (class "Default")
      (node (ref "IC5") (pin "4") (pinfunction "X7_4") (pintype "bidirectional"))
      (node (ref "OS9") (pin "C") (pinfunction "COLLECTOR_C") (pintype "passive"))
      (node (ref "R19") (pin "1") (pinfunction "1_1") (pintype "passive"))
    )
    (net (code "21") (name "Net-(IC6A-X0)") (class "Default")
      (node (ref "IC6") (pin "13") (pinfunction "X0_13") (pintype "bidirectional"))
      (node (ref "OS10") (pin "C") (pinfunction "COLLECTOR_C") (pintype "passive"))
      (node (ref "R22") (pin "1") (pinfunction "1_1") (pintype "passive"))
    )
    (net (code "22") (name "Net-(IC6A-X1)") (class "Default")
      (node (ref "IC6") (pin "14") (pinfunction "X1_14") (pintype "bidirectional"))
      (node (ref "OS11") (pin "C") (pinfunction "COLLECTOR_C") (pintype "passive"))
      (node (ref "R24") (pin "1") (pinfunction "1_1") (pintype "passive"))
    )
    (net (code "23") (name "Net-(IC6A-X2)") (class "Default")
      (node (ref "IC6") (pin "15") (pinfunction "X2_15") (pintype "bidirectional"))
      (node (ref "OS12") (pin "C") (pinfunction "COLLECTOR_C") (pintype "passive"))
      (node (ref "R26") (pin "1") (pinfunction "1_1") (pintype "passive"))
    )
    (net (code "24") (name "Net-(IC6A-X3)") (class "Default")
      (node (ref "IC6") (pin "12") (pinfunction "X3_12") (pintype "bidirectional"))
      (node (ref "OS13") (pin "C") (pinfunction "COLLECTOR_C") (pintype "passive"))
      (node (ref "R28") (pin "1") (pinfunction "1_1") (pintype "passive"))
    )
    (net (code "25") (name "Net-(IC6A-X4)") (class "Default")
      (node (ref "IC6") (pin "1") (pinfunction "X4_1") (pintype "bidirectional"))
      (node (ref "OS14") (pin "C") (pinfunction "COLLECTOR_C") (pintype "passive"))
      (node (ref "R30") (pin "1") (pinfunction "1_1") (pintype "passive"))
    )
    (net (code "26") (name "Net-(IC6A-X5)") (class "Default")
      (node (ref "IC6") (pin "5") (pinfunction "X5_5") (pintype "bidirectional"))
      (node (ref "OS15") (pin "C") (pinfunction "COLLECTOR_C") (pintype "passive"))
      (node (ref "R32") (pin "1") (pinfunction "1_1") (pintype "passive"))
    )
    (net (code "27") (name "Net-(IC6A-X6)") (class "Default")
      (node (ref "IC6") (pin "2") (pinfunction "X6_2") (pintype "bidirectional"))
      (node (ref "OS16") (pin "C") (pinfunction "COLLECTOR_C") (pintype "passive"))
      (node (ref "R34") (pin "1") (pinfunction "1_1") (pintype "passive"))
    )
    (net (code "28") (name "Net-(IC6A-X7)") (class "Default")
      (node (ref "IC6") (pin "4") (pinfunction "X7_4") (pintype "bidirectional"))
      (node (ref "OS17") (pin "C") (pinfunction "COLLECTOR_C") (pintype "passive"))
      (node (ref "R36") (pin "1") (pinfunction "1_1") (pintype "passive"))
    )
    (net (code "29") (name "Net-(IC7A-X0)") (class "Default")
      (node (ref "IC7") (pin "13") (pinfunction "X0_13") (pintype "bidirectional"))
      (node (ref "OS18") (pin "C") (pinfunction "COLLECTOR_C") (pintype "passive"))
      (node (ref "R39") (pin "1") (pinfunction "1_1") (pintype "passive"))
    )
    (net (code "30") (name "Net-(IC7A-X1)") (class "Default")
      (node (ref "IC7") (pin "14") (pinfunction "X1_14") (pintype "bidirectional"))
      (node (ref "OS19") (pin "C") (pinfunction "COLLECTOR_C") (pintype "passive"))
      (node (ref "R41") (pin "1") (pinfunction "1_1") (pintype "passive"))
    )
    (net (code "31") (name "Net-(IC7A-X2)") (class "Default")
      (node (ref "IC7") (pin "15") (pinfunction "X2_15") (pintype "bidirectional"))
      (node (ref "OS20") (pin "C") (pinfunction "COLLECTOR_C") (pintype "passive"))
      (node (ref "R43") (pin "1") (pinfunction "1_1") (pintype "passive"))
    )
    (net (code "32") (name "Net-(IC7A-X3)") (class "Default")
      (node (ref "IC7") (pin "12") (pinfunction "X3_12") (pintype "bidirectional"))
      (node (ref "OS21") (pin "C") (pinfunction "COLLECTOR_C") (pintype "passive"))
      (node (ref "R45") (pin "1") (pinfunction "1_1") (pintype "passive"))
    )
    (net (code "33") (name "Net-(IC7A-X4)") (class "Default")
      (node (ref "IC7") (pin "1") (pinfunction "X4_1") (pintype "bidirectional"))
      (node (ref "OS22") (pin "C") (pinfunction "COLLECTOR_C") (pintype "passive"))
      (node (ref "R47") (pin "1") (pinfunction "1_1") (pintype "passive"))
    )
    (net (code "34") (name "Net-(IC7A-X5)") (class "Default")
      (node (ref "IC7") (pin "5") (pinfunction "X5_5") (pintype "bidirectional"))
      (node (ref "OS23") (pin "C") (pinfunction "COLLECTOR_C") (pintype "passive"))
      (node (ref "R49") (pin "1") (pinfunction "1_1") (pintype "passive"))
    )
    (net (code "35") (name "Net-(IC7A-X6)") (class "Default")
      (node (ref "IC7") (pin "2") (pinfunction "X6_2") (pintype "bidirectional"))
      (node (ref "OS24") (pin "C") (pinfunction "COLLECTOR_C") (pintype "passive"))
      (node (ref "R51") (pin "1") (pinfunction "1_1") (pintype "passive"))
    )
    (net (code "36") (name "Net-(IC7A-X7)") (class "Default")
      (node (ref "IC7") (pin "4") (pinfunction "X7_4") (pintype "bidirectional"))
      (node (ref "OS25") (pin "C") (pinfunction "COLLECTOR_C") (pintype "passive"))
      (node (ref "R53") (pin "1") (pinfunction "1_1") (pintype "passive"))
    )
    (net (code "37") (name "Net-(LED1-DO)") (class "Default")
      (node (ref "LED1") (pin "D_OUT") (pinfunction "DO_D_OUT") (pintype "output"))
      (node (ref "LED2") (pin "D_IN") (pinfunction "DI_D_IN") (pintype "input"))
    )
    (net (code "38") (name "Net-(LED2-DO)") (class "Default")
      (node (ref "LED2") (pin "D_OUT") (pinfunction "DO_D_OUT") (pintype "output"))
      (node (ref "LED3") (pin "D_IN") (pinfunction "DI_D_IN") (pintype "input"))
    )
    (net (code "39") (name "Net-(LED3-DO)") (class "Default")
      (node (ref "LED3") (pin "D_OUT") (pinfunction "DO_D_OUT") (pintype "output"))
      (node (ref "LED4") (pin "D_IN") (pinfunction "DI_D_IN") (pintype "input"))
    )
    (net (code "40") (name "Net-(LED4-DO)") (class "Default")
      (node (ref "LED4") (pin "D_OUT") (pinfunction "DO_D_OUT") (pintype "output"))
      (node (ref "LED5") (pin "D_IN") (pinfunction "DI_D_IN") (pintype "input"))
    )
    (net (code "41") (name "Net-(LED6-DO)") (class "Default")
      (node (ref "LED6") (pin "D_OUT") (pinfunction "DO_D_OUT") (pintype "output"))
      (node (ref "LED7") (pin "D_IN") (pinfunction "DI_D_IN") (pintype "input"))
    )
    (net (code "42") (name "Net-(LED7-DO)") (class "Default")
      (node (ref "LED7") (pin "D_OUT") (pinfunction "DO_D_OUT") (pintype "output"))
      (node (ref "LED8") (pin "D_IN") (pinfunction "DI_D_IN") (pintype "input"))
    )
    (net (code "43") (name "Net-(LED8-DO)") (class "Default")
      (node (ref "LED8") (pin "D_OUT") (pinfunction "DO_D_OUT") (pintype "output"))
      (node (ref "LED9") (pin "D_IN") (pinfunction "DI_D_IN") (pintype "input"))
    )
    (net (code "44") (name "Net-(LED10-DI)") (class "Default")
      (node (ref "LED10") (pin "D_IN") (pinfunction "DI_D_IN") (pintype "input"))
      (node (ref "LED9") (pin "D_OUT") (pinfunction "DO_D_OUT") (pintype "output"))
    )
    (net (code "45") (name "Net-(LED11-DO)") (class "Default")
      (node (ref "LED11") (pin "D_OUT") (pinfunction "DO_D_OUT") (pintype "output"))
      (node (ref "LED12") (pin "D_IN") (pinfunction "DI_D_IN") (pintype "input"))
    )
    (net (code "46") (name "Net-(LED12-DO)") (class "Default")
      (node (ref "LED12") (pin "D_OUT") (pinfunction "DO_D_OUT") (pintype "output"))
      (node (ref "LED13") (pin "D_IN") (pinfunction "DI_D_IN") (pintype "input"))
    )
    (net (code "47") (name "Net-(LED13-DO)") (class "Default")
      (node (ref "LED13") (pin "D_OUT") (pinfunction "DO_D_OUT") (pintype "output"))
      (node (ref "LED14") (pin "D_IN") (pinfunction "DI_D_IN") (pintype "input"))
    )
    (net (code "48") (name "Net-(LED14-DO)") (class "Default")
      (node (ref "LED14") (pin "D_OUT") (pinfunction "DO_D_OUT") (pintype "output"))
      (node (ref "LED15") (pin "D_IN") (pinfunction "DI_D_IN") (pintype "input"))
    )
    (net (code "49") (name "Net-(LED16-DO)") (class "Default")
      (node (ref "LED16") (pin "D_OUT") (pinfunction "DO_D_OUT") (pintype "output"))
      (node (ref "LED17") (pin "D_IN") (pinfunction "DI_D_IN") (pintype "input"))
    )
    (net (code "50") (name "Net-(LED17-DO)") (class "Default")
      (node (ref "LED17") (pin "D_OUT") (pinfunction "DO_D_OUT") (pintype "output"))
      (node (ref "LED18") (pin "D_IN") (pinfunction "DI_D_IN") (pintype "input"))
    )
    (net (code "51") (name "Net-(LED18-DO)") (class "Default")
      (node (ref "LED18") (pin "D_OUT") (pinfunction "DO_D_OUT") (pintype "output"))
      (node (ref "LED19") (pin "D_IN") (pinfunction "DI_D_IN") (pintype "input"))
    )
    (net (code "52") (name "Net-(LED19-DO)") (class "Default")
      (node (ref "LED19") (pin "D_OUT") (pinfunction "DO_D_OUT") (pintype "output"))
      (node (ref "LED20") (pin "D_IN") (pinfunction "DI_D_IN") (pintype "input"))
    )
    (net (code "53") (name "Net-(LED21-DO)") (class "Default")
      (node (ref "LED21") (pin "D_OUT") (pinfunction "DO_D_OUT") (pintype "output"))
      (node (ref "LED22") (pin "D_IN") (pinfunction "DI_D_IN") (pintype "input"))
    )
    (net (code "54") (name "Net-(LED22-DO)") (class "Default")
      (node (ref "LED22") (pin "D_OUT") (pinfunction "DO_D_OUT") (pintype "output"))
      (node (ref "LED23") (pin "D_IN") (pinfunction "DI_D_IN") (pintype "input"))
    )
    (net (code "55") (name "Net-(LED23-DO)") (class "Default")
      (node (ref "LED23") (pin "D_OUT") (pinfunction "DO_D_OUT") (pintype "output"))
      (node (ref "LED24") (pin "D_IN") (pinfunction "DI_D_IN") (pintype "input"))
    )
    (net (code "56") (name "Net-(LED24-DO)") (class "Default")
      (node (ref "LED24") (pin "D_OUT") (pinfunction "DO_D_OUT") (pintype "output"))
      (node (ref "LED25") (pin "D_IN") (pinfunction "DI_D_IN") (pintype "input"))
    )
    (net (code "57") (name "Net-(OS2-ANODE)") (class "Default")
      (node (ref "OS2") (pin "A") (pinfunction "ANODE_A") (pintype "passive"))
      (node (ref "R8") (pin "1") (pinfunction "1_1") (pintype "passive"))
    )
    (net (code "58") (name "Net-(OS3-ANODE)") (class "Default")
      (node (ref "OS3") (pin "A") (pinfunction "ANODE_A") (pintype "passive"))
      (node (ref "R10") (pin "1") (pinfunction "1_1") (pintype "passive"))
    )
    (net (code "59") (name "Net-(OS4-ANODE)") (class "Default")
      (node (ref "OS4") (pin "A") (pinfunction "ANODE_A") (pintype "passive"))
      (node (ref "R6") (pin "1") (pinfunction "1_1") (pintype "passive"))
    )
    (net (code "60") (name "Net-(OS5-ANODE)") (class "Default")
      (node (ref "OS5") (pin "A") (pinfunction "ANODE_A") (pintype "passive"))
      (node (ref "R12") (pin "1") (pinfunction "1_1") (pintype "passive"))
    )
    (net (code "61") (name "Net-(OS6-ANODE)") (class "Default")
      (node (ref "OS6") (pin "A") (pinfunction "ANODE_A") (pintype "passive"))
      (node (ref "R14") (pin "1") (pinfunction "1_1") (pintype "passive"))
    )
    (net (code "62") (name "Net-(OS7-ANODE)") (class "Default")
      (node (ref "OS7") (pin "A") (pinfunction "ANODE_A") (pintype "passive"))
      (node (ref "R16") (pin "1") (pinfunction "1_1") (pintype "passive"))
    )
    (net (code "63") (name "Net-(OS8-ANODE)") (class "Default")
      (node (ref "OS8") (pin "A") (pinfunction "ANODE_A") (pintype "passive"))
      (node (ref "R18") (pin "1") (pinfunction "1_1") (pintype "passive"))
    )
    (net (code "64") (name "Net-(OS9-ANODE)") (class "Default")
      (node (ref "OS9") (pin "A") (pinfunction "ANODE_A") (pintype "passive"))
      (node (ref "R20") (pin "1") (pinfunction "1_1") (pintype "passive"))
    )
    (net (code "65") (name "Net-(OS10-ANODE)") (class "Default")
      (node (ref "OS10") (pin "A") (pinfunction "ANODE_A") (pintype "passive"))
      (node (ref "R23") (pin "1") (pinfunction "1_1") (pintype "passive"))
    )
    (net (code "66") (name "Net-(OS11-ANODE)") (class "Default")
      (node (ref "OS11") (pin "A") (pinfunction "ANODE_A") (pintype "passive"))
      (node (ref "R25") (pin "1") (pinfunction "1_1") (pintype "passive"))
    )
    (net (code "67") (name "Net-(OS12-ANODE)") (class "Default")
      (node (ref "OS12") (pin "A") (pinfunction "ANODE_A") (pintype "passive"))
      (node (ref "R27") (pin "1") (pinfunction "1_1") (pintype "passive"))
    )
    (net (code "68") (name "Net-(OS13-ANODE)") (class "Default")
      (node (ref "OS13") (pin "A") (pinfunction "ANODE_A") (pintype "passive"))
      (node (ref "R29") (pin "1") (pinfunction "1_1") (pintype "passive"))
    )
    (net (code "69") (name "Net-(OS14-ANODE)") (class "Default")
      (node (ref "OS14") (pin "A") (pinfunction "ANODE_A") (pintype "passive"))
      (node (ref "R31") (pin "1") (pinfunction "1_1") (pintype "passive"))
    )
    (net (code "70") (name "Net-(OS15-ANODE)") (class "Default")
      (node (ref "OS15") (pin "A") (pinfunction "ANODE_A") (pintype "passive"))
      (node (ref "R33") (pin "1") (pinfunction "1_1") (pintype "passive"))
    )
    (net (code "71") (name "Net-(OS16-ANODE)") (class "Default")
      (node (ref "OS16") (pin "A") (pinfunction "ANODE_A") (pintype "passive"))
      (node (ref "R35") (pin "1") (pinfunction "1_1") (pintype "passive"))
    )
    (net (code "72") (name "Net-(OS17-ANODE)") (class "Default")
      (node (ref "OS17") (pin "A") (pinfunction "ANODE_A") (pintype "passive"))
      (node (ref "R37") (pin "1") (pinfunction "1_1") (pintype "passive"))
    )
    (net (code "73") (name "Net-(OS18-ANODE)") (class "Default")
      (node (ref "OS18") (pin "A") (pinfunction "ANODE_A") (pintype "passive"))
      (node (ref "R40") (pin "1") (pinfunction "1_1") (pintype "passive"))
    )
    (net (code "74") (name "Net-(OS19-ANODE)") (class "Default")
      (node (ref "OS19") (pin "A") (pinfunction "ANODE_A") (pintype "passive"))
      (node (ref "R42") (pin "1") (pinfunction "1_1") (pintype "passive"))
    )
    (net (code "75") (name "Net-(OS20-ANODE)") (class "Default")
      (node (ref "OS20") (pin "A") (pinfunction "ANODE_A") (pintype "passive"))
      (node (ref "R44") (pin "1") (pinfunction "1_1") (pintype "passive"))
    )
    (net (code "76") (name "Net-(OS21-ANODE)") (class "Default")
      (node (ref "OS21") (pin "A") (pinfunction "ANODE_A") (pintype "passive"))
      (node (ref "R46") (pin "1") (pinfunction "1_1") (pintype "passive"))
    )
    (net (code "77") (name "Net-(OS22-ANODE)") (class "Default")
      (node (ref "OS22") (pin "A") (pinfunction "ANODE_A") (pintype "passive"))
      (node (ref "R48") (pin "1") (pinfunction "1_1") (pintype "passive"))
    )
    (net (code "78") (name "Net-(OS23-ANODE)") (class "Default")
      (node (ref "OS23") (pin "A") (pinfunction "ANODE_A") (pintype "passive"))
      (node (ref "R50") (pin "1") (pinfunction "1_1") (pintype "passive"))
    )
    (net (code "79") (name "Net-(OS24-ANODE)") (class "Default")
      (node (ref "OS24") (pin "A") (pinfunction "ANODE_A") (pintype "passive"))
      (node (ref "R52") (pin "1") (pinfunction "1_1") (pintype "passive"))
    )
    (net (code "80") (name "Net-(OS25-ANODE)") (class "Default")
      (node (ref "OS25") (pin "A") (pinfunction "ANODE_A") (pintype "passive"))
      (node (ref "R54") (pin "1") (pinfunction "1_1") (pintype "passive"))
    )
    (net (code "81") (name "Net-(OS26-ANODE)") (class "Default")
      (node (ref "OS26") (pin "A") (pinfunction "ANODE_A") (pintype "passive"))
      (node (ref "R57") (pin "1") (pinfunction "1_1") (pintype "passive"))
    )
    (net (code "82") (name "Net-(Q2-D)") (class "Default")
      (node (ref "Q2") (pin "4") (pinfunction "D_4") (pintype "passive"))
      (node (ref "R10") (pin "2") (pinfunction "2_2") (pintype "passive"))
      (node (ref "R11") (pin "2") (pinfunction "2_2") (pintype "passive"))
      (node (ref "R12") (pin "2") (pinfunction "2_2") (pintype "passive"))
      (node (ref "R13") (pin "2") (pinfunction "2_2") (pintype "passive"))
      (node (ref "R14") (pin "2") (pinfunction "2_2") (pintype "passive"))
      (node (ref "R15") (pin "2") (pinfunction "2_2") (pintype "passive"))
      (node (ref "R16") (pin "2") (pinfunction "2_2") (pintype "passive"))
      (node (ref "R17") (pin "2") (pinfunction "2_2") (pintype "passive"))
      (node (ref "R18") (pin "2") (pinfunction "2_2") (pintype "passive"))
      (node (ref "R19") (pin "2") (pinfunction "2_2") (pintype "passive"))
      (node (ref "R20") (pin "2") (pinfunction "2_2") (pintype "passive"))
      (node (ref "R5") (pin "2") (pinfunction "2_2") (pintype "passive"))
      (node (ref "R6") (pin "2") (pinfunction "2_2") (pintype "passive"))
      (node (ref "R7") (pin "2") (pinfunction "2_2") (pintype "passive"))
      (node (ref "R8") (pin "2") (pinfunction "2_2") (pintype "passive"))
      (node (ref "R9") (pin "2") (pinfunction "2_2") (pintype "passive"))
    )
    (net (code "83") (name "Net-(Q3-D)") (class "Default")
      (node (ref "Q3") (pin "4") (pinfunction "D_4") (pintype "passive"))
      (node (ref "R22") (pin "2") (pinfunction "2_2") (pintype "passive"))
      (node (ref "R23") (pin "2") (pinfunction "2_2") (pintype "passive"))
      (node (ref "R24") (pin "2") (pinfunction "2_2") (pintype "passive"))
      (node (ref "R25") (pin "2") (pinfunction "2_2") (pintype "passive"))
      (node (ref "R26") (pin "2") (pinfunction "2_2") (pintype "passive"))
      (node (ref "R27") (pin "2") (pinfunction "2_2") (pintype "passive"))
      (node (ref "R28") (pin "2") (pinfunction "2_2") (pintype "passive"))
      (node (ref "R29") (pin "2") (pinfunction "2_2") (pintype "passive"))
      (node (ref "R30") (pin "2") (pinfunction "2_2") (pintype "passive"))
      (node (ref "R31") (pin "2") (pinfunction "2_2") (pintype "passive"))
      (node (ref "R32") (pin "2") (pinfunction "2_2") (pintype "passive"))
      (node (ref "R33") (pin "2") (pinfunction "2_2") (pintype "passive"))
      (node (ref "R34") (pin "2") (pinfunction "2_2") (pintype "passive"))
      (node (ref "R35") (pin "2") (pinfunction "2_2") (pintype "passive"))
      (node (ref "R36") (pin "2") (pinfunction "2_2") (pintype "passive"))
      (node (ref "R37") (pin "2") (pinfunction "2_2") (pintype "passive"))
    )
    (net (code "84") (name "Net-(Q4-D)") (class "Default")
      (node (ref "Q4") (pin "4") (pinfunction "D_4") (pintype "passive"))
      (node (ref "R39") (pin "2") (pinfunction "2_2") (pintype "passive"))
      (node (ref "R40") (pin "2") (pinfunction "2_2") (pintype "passive"))
      (node (ref "R41") (pin "2") (pinfunction "2_2") (pintype "passive"))
      (node (ref "R42") (pin "2") (pinfunction "2_2") (pintype "passive"))
      (node (ref "R43") (pin "2") (pinfunction "2_2") (pintype "passive"))
      (node (ref "R44") (pin "2") (pinfunction "2_2") (pintype "passive"))
      (node (ref "R45") (pin "2") (pinfunction "2_2") (pintype "passive"))
      (node (ref "R46") (pin "2") (pinfunction "2_2") (pintype "passive"))
      (node (ref "R47") (pin "2") (pinfunction "2_2") (pintype "passive"))
      (node (ref "R48") (pin "2") (pinfunction "2_2") (pintype "passive"))
      (node (ref "R49") (pin "2") (pinfunction "2_2") (pintype "passive"))
      (node (ref "R50") (pin "2") (pinfunction "2_2") (pintype "passive"))
      (node (ref "R51") (pin "2") (pinfunction "2_2") (pintype "passive"))
      (node (ref "R52") (pin "2") (pinfunction "2_2") (pintype "passive"))
      (node (ref "R53") (pin "2") (pinfunction "2_2") (pintype "passive"))
      (node (ref "R54") (pin "2") (pinfunction "2_2") (pintype "passive"))
      (node (ref "R56") (pin "2") (pinfunction "2_2") (pintype "passive"))
      (node (ref "R57") (pin "2") (pinfunction "2_2") (pintype "passive"))
    )
    (net (code "85") (name "SECTION_1_EN") (class "Default")
      (node (ref "IC4") (pin "1") (pinfunction "Y0_1") (pintype "bidirectional"))
      (node (ref "Q2") (pin "1") (pinfunction "G_1") (pintype "passive"))
      (node (ref "R21") (pin "1") (pinfunction "1_1") (pintype "passive"))
    )
    (net (code "86") (name "SECTION_2_EN") (class "Default")
      (node (ref "IC4") (pin "5") (pinfunction "Y1_5") (pintype "bidirectional"))
      (node (ref "Q3") (pin "1") (pinfunction "G_1") (pintype "passive"))
      (node (ref "R38") (pin "1") (pinfunction "1_1") (pintype "passive"))
    )
    (net (code "87") (name "SECTION_3_EN") (class "Default")
      (node (ref "IC4") (pin "2") (pinfunction "Y2_2") (pintype "bidirectional"))
      (node (ref "IC4") (pin "4") (pinfunction "Y3_4") (pintype "bidirectional"))
      (node (ref "Q4") (pin "1") (pinfunction "G_1") (pintype "passive"))
      (node (ref "R55") (pin "1") (pinfunction "1_1") (pintype "passive"))
    )
    (net (code "88") (name "SENSOR") (class "Default")
      (node (ref "IC4") (pin "13") (pinfunction "X_13") (pintype "bidirectional"))
      (node (ref "J1") (pin "6") (pinfunction "6_6") (pintype "passive"))
    )
    (net (code "89") (name "unconnected-(LED1-DI-PadD_IN)") (class "Default")
      (node (ref "LED1") (pin "D_IN") (pinfunction "DI_D_IN") (pintype "input"))
    )
    (net (code "90") (name "unconnected-(LED5-DO-PadD_OUT)") (class "Default")
      (node (ref "LED5") (pin "D_OUT") (pinfunction "DO_D_OUT") (pintype "output"))
    )
    (net (code "91") (name "unconnected-(LED6-DI-PadD_IN)") (class "Default")
      (node (ref "LED6") (pin "D_IN") (pinfunction "DI_D_IN") (pintype "input"))
    )
    (net (code "92") (name "unconnected-(LED10-DO-PadD_OUT)") (class "Default")
      (node (ref "LED10") (pin "D_OUT") (pinfunction "DO_D_OUT") (pintype "output"))
    )
    (net (code "93") (name "unconnected-(LED11-DI-PadD_IN)") (class "Default")
      (node (ref "LED11") (pin "D_IN") (pinfunction "DI_D_IN") (pintype "input"))
    )
    (net (code "94") (name "unconnected-(LED15-DO-PadD_OUT)") (class "Default")
      (node (ref "LED15") (pin "D_OUT") (pinfunction "DO_D_OUT") (pintype "output"))
    )
    (net (code "95") (name "unconnected-(LED16-DI-PadD_IN)") (class "Default")
      (node (ref "LED16") (pin "D_IN") (pinfunction "DI_D_IN") (pintype "input"))
    )
    (net (code "96") (name "unconnected-(LED20-DO-PadD_OUT)") (class "Default")
      (node (ref "LED20") (pin "D_OUT") (pinfunction "DO_D_OUT") (pintype "output"))
    )
    (net (code "97") (name "unconnected-(LED21-DI-PadD_IN)") (class "Default")
      (node (ref "LED21") (pin "D_IN") (pinfunction "DI_D_IN") (pintype "input"))
    )
    (net (code "98") (name "unconnected-(LED25-DO-PadD_OUT)") (class "Default")
      (node (ref "LED25") (pin "D_OUT") (pinfunction "DO_D_OUT") (pintype "output"))
    )
  )
)
